# elements_v02.net
KiCad netlist of a schematic drawn in EAGLE
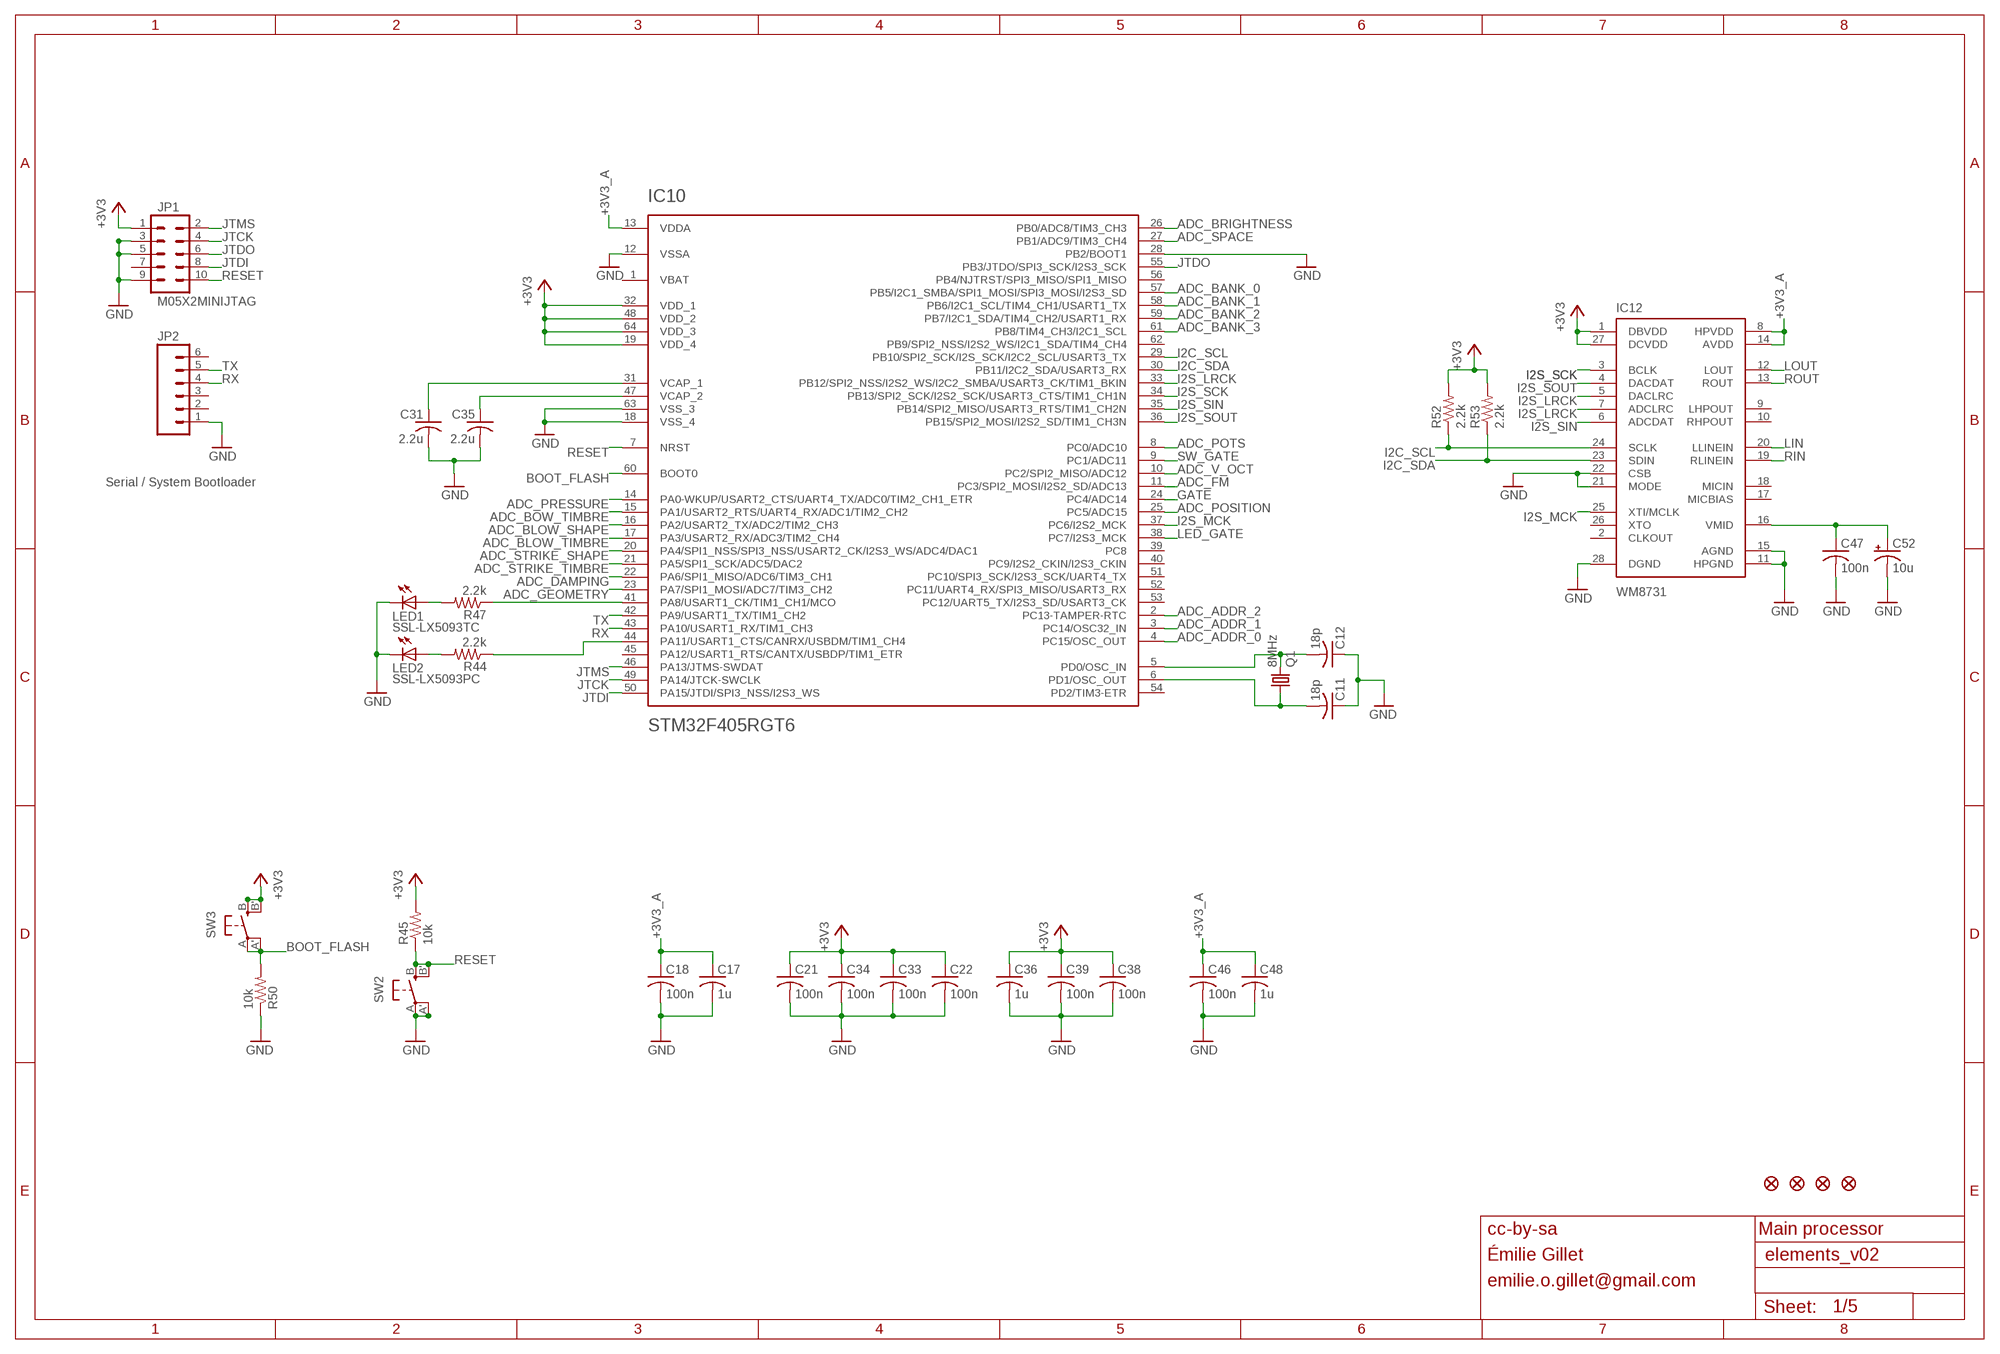
[diagram p0: schematic, sheet 1]
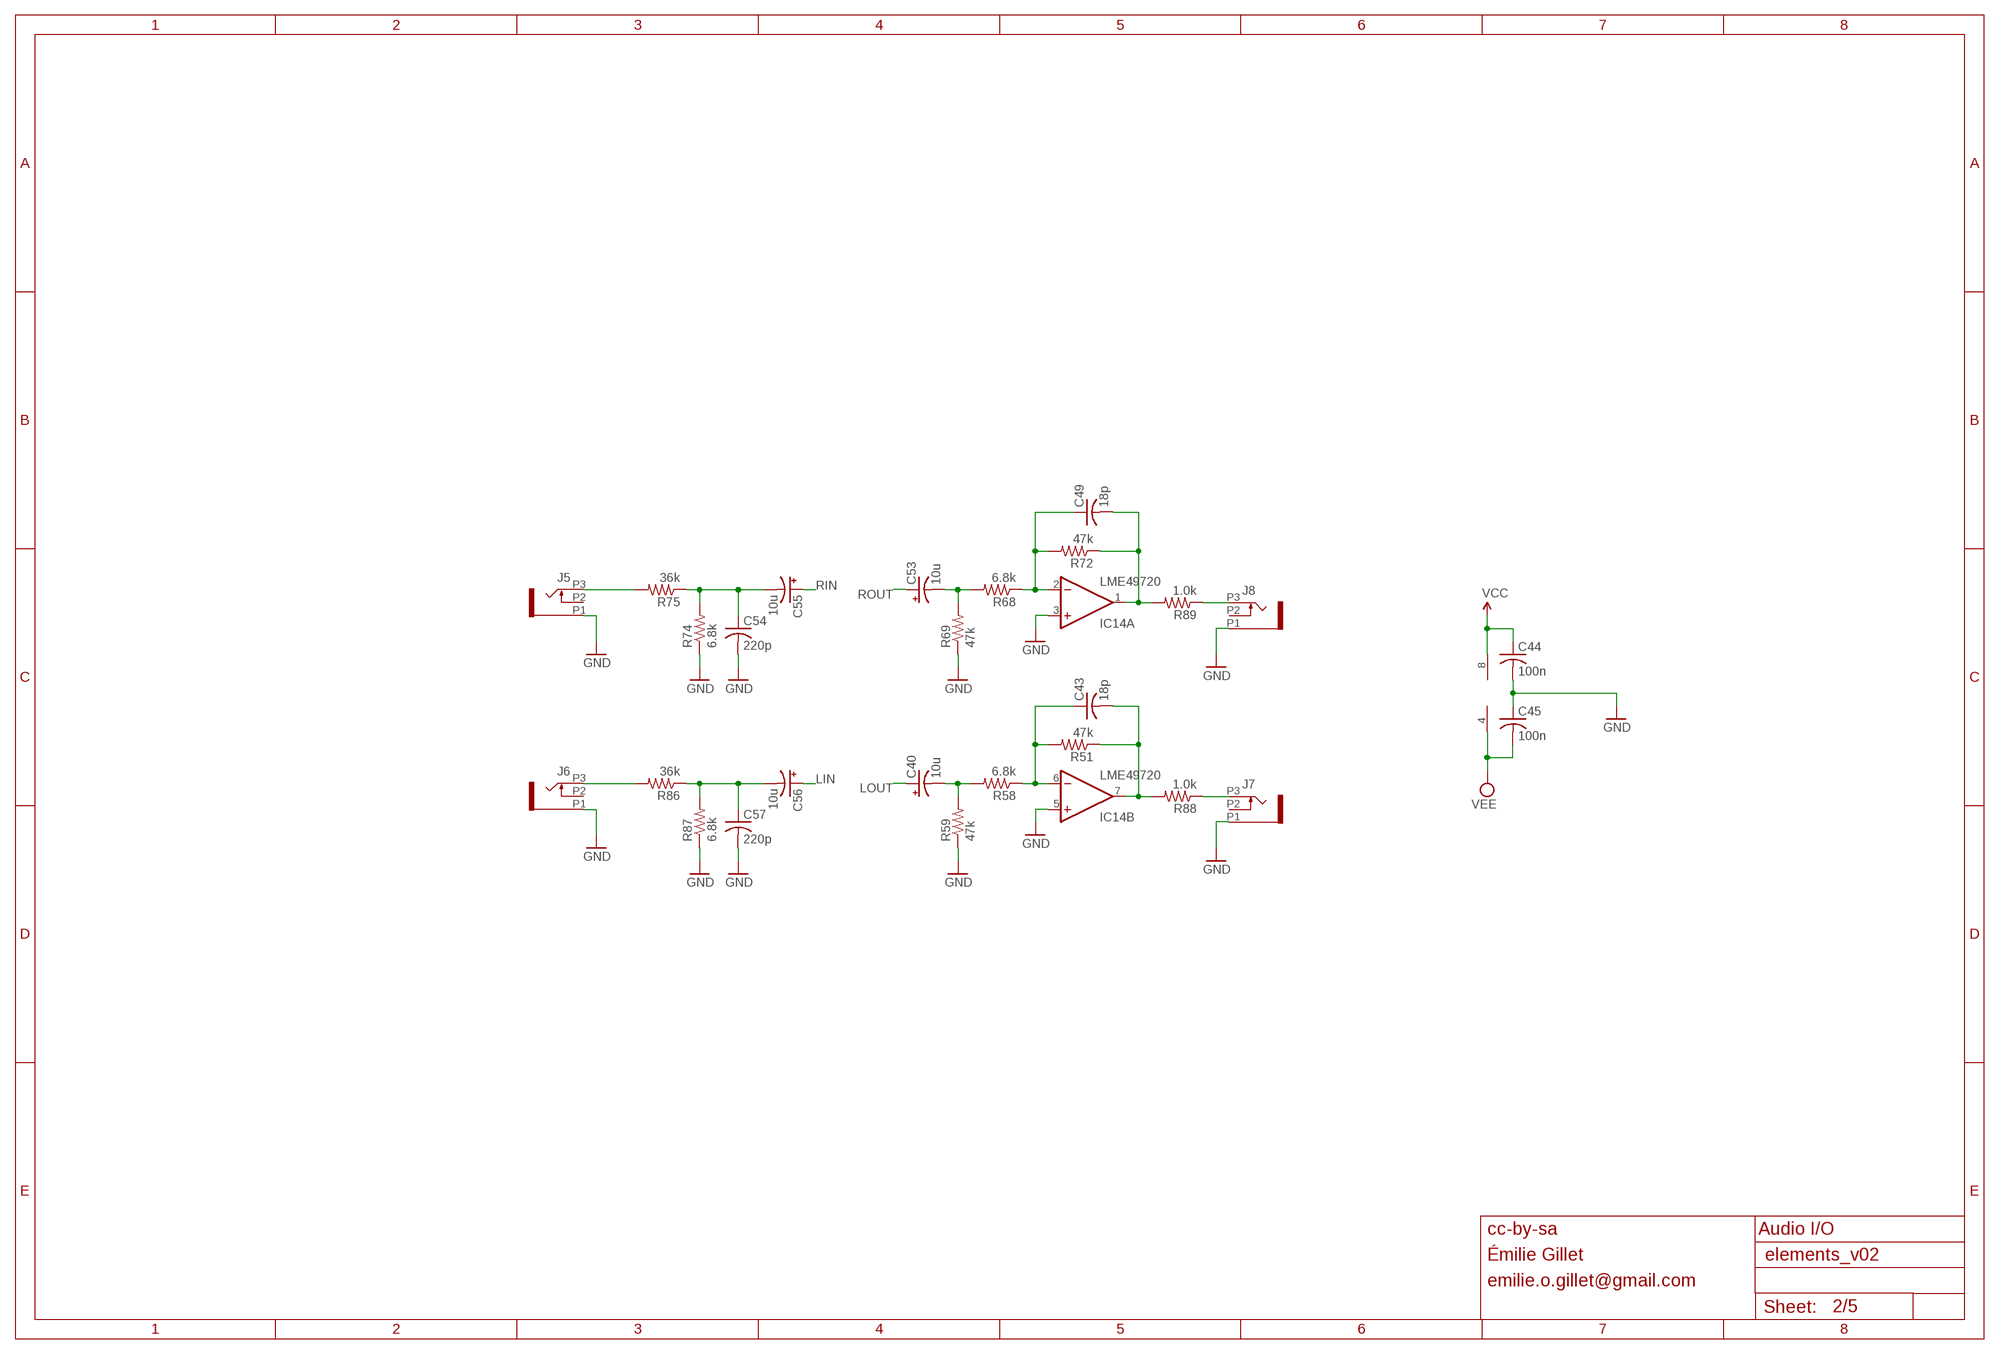
[diagram p1: schematic, sheet 2]
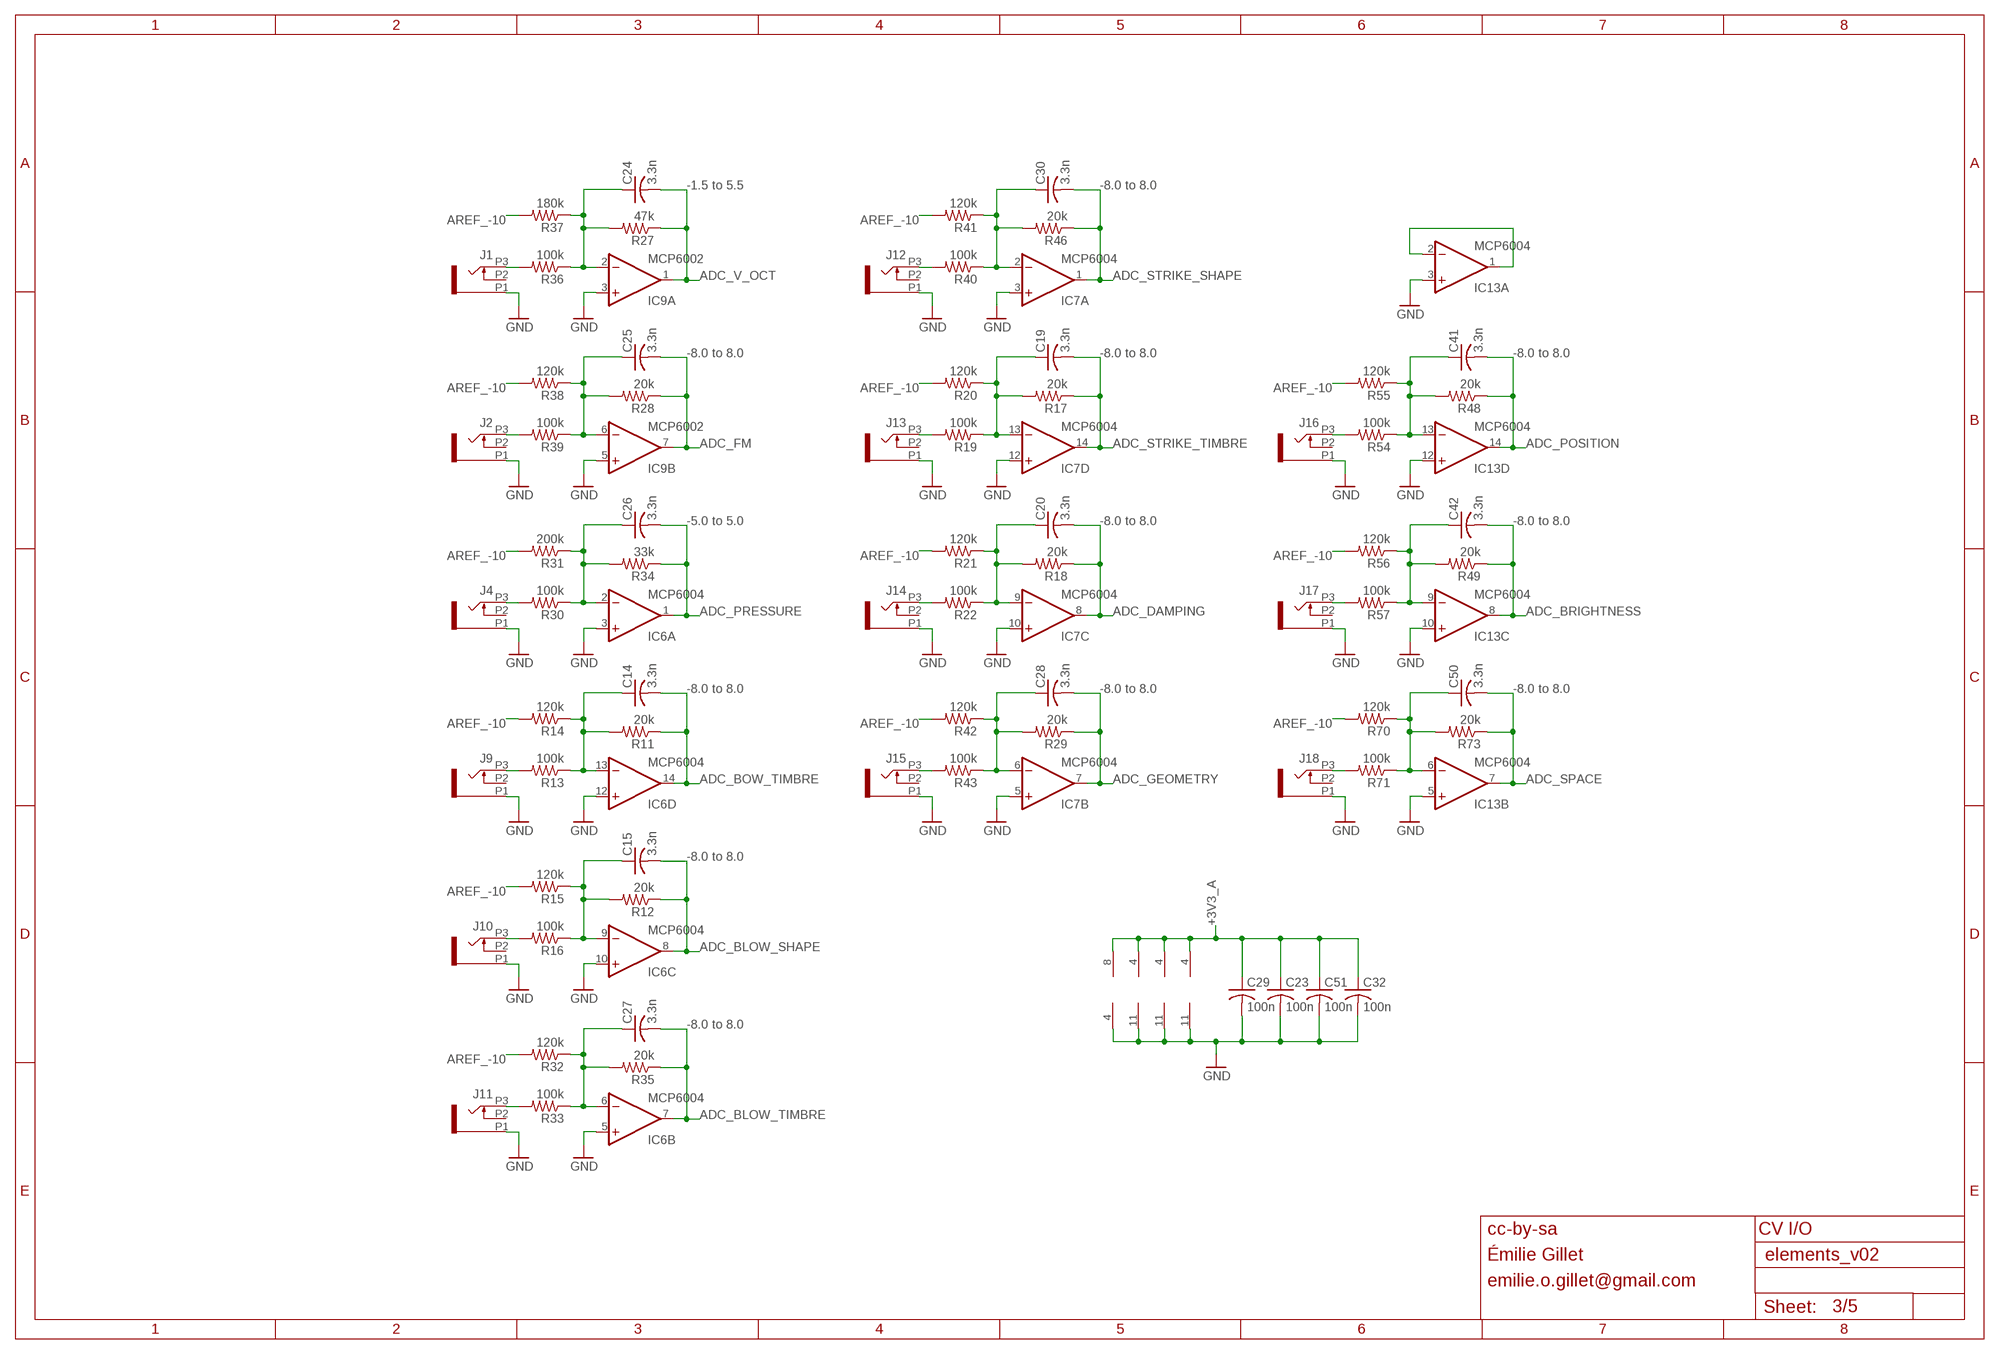
[diagram p2: schematic, sheet 3]
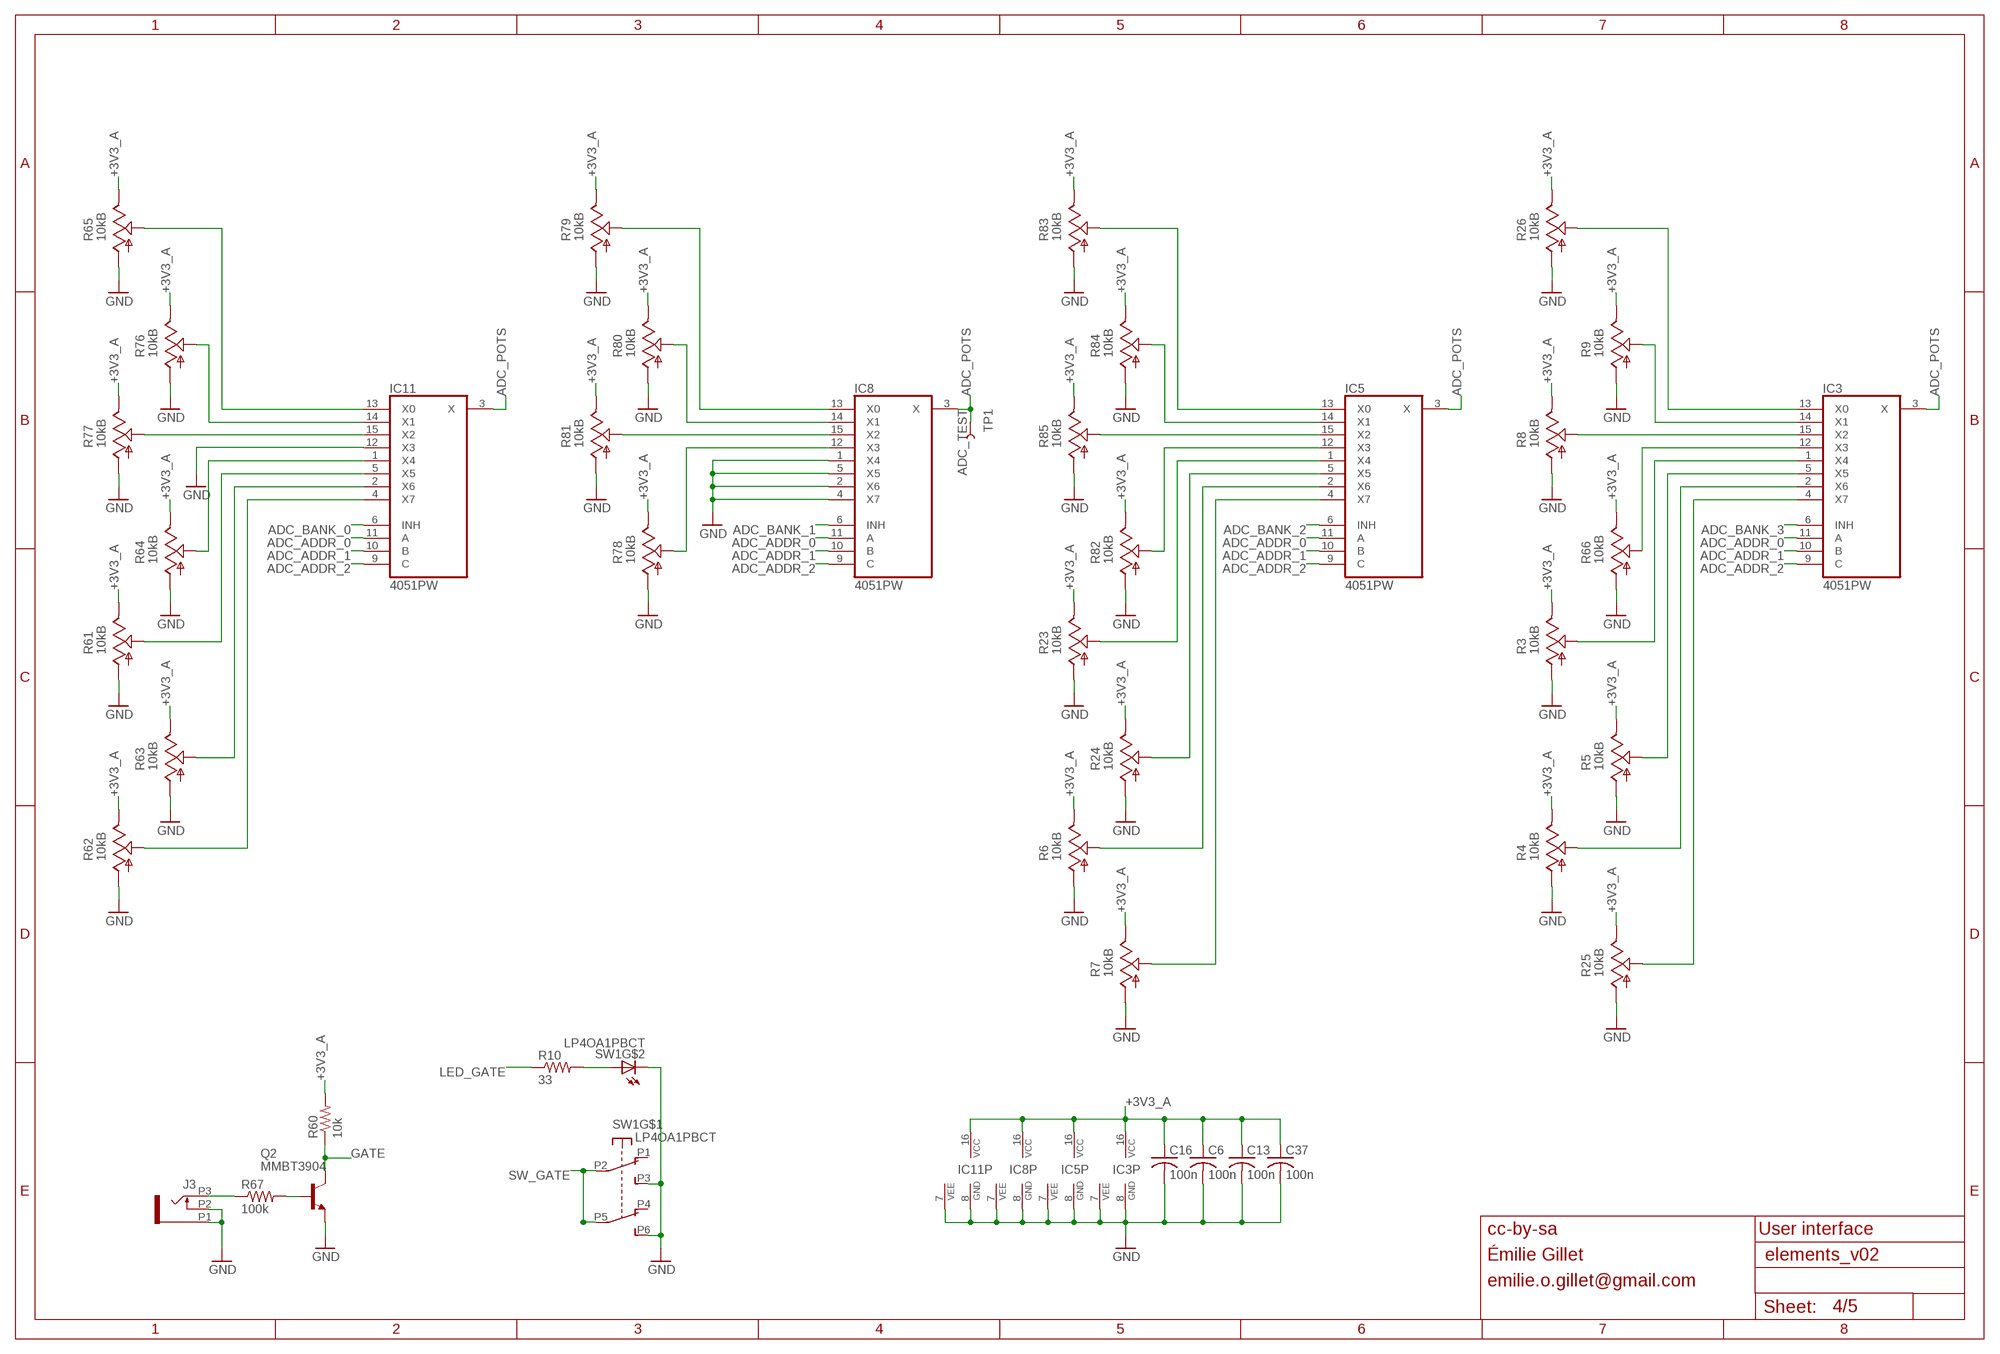
[diagram p3: schematic, sheet 4]
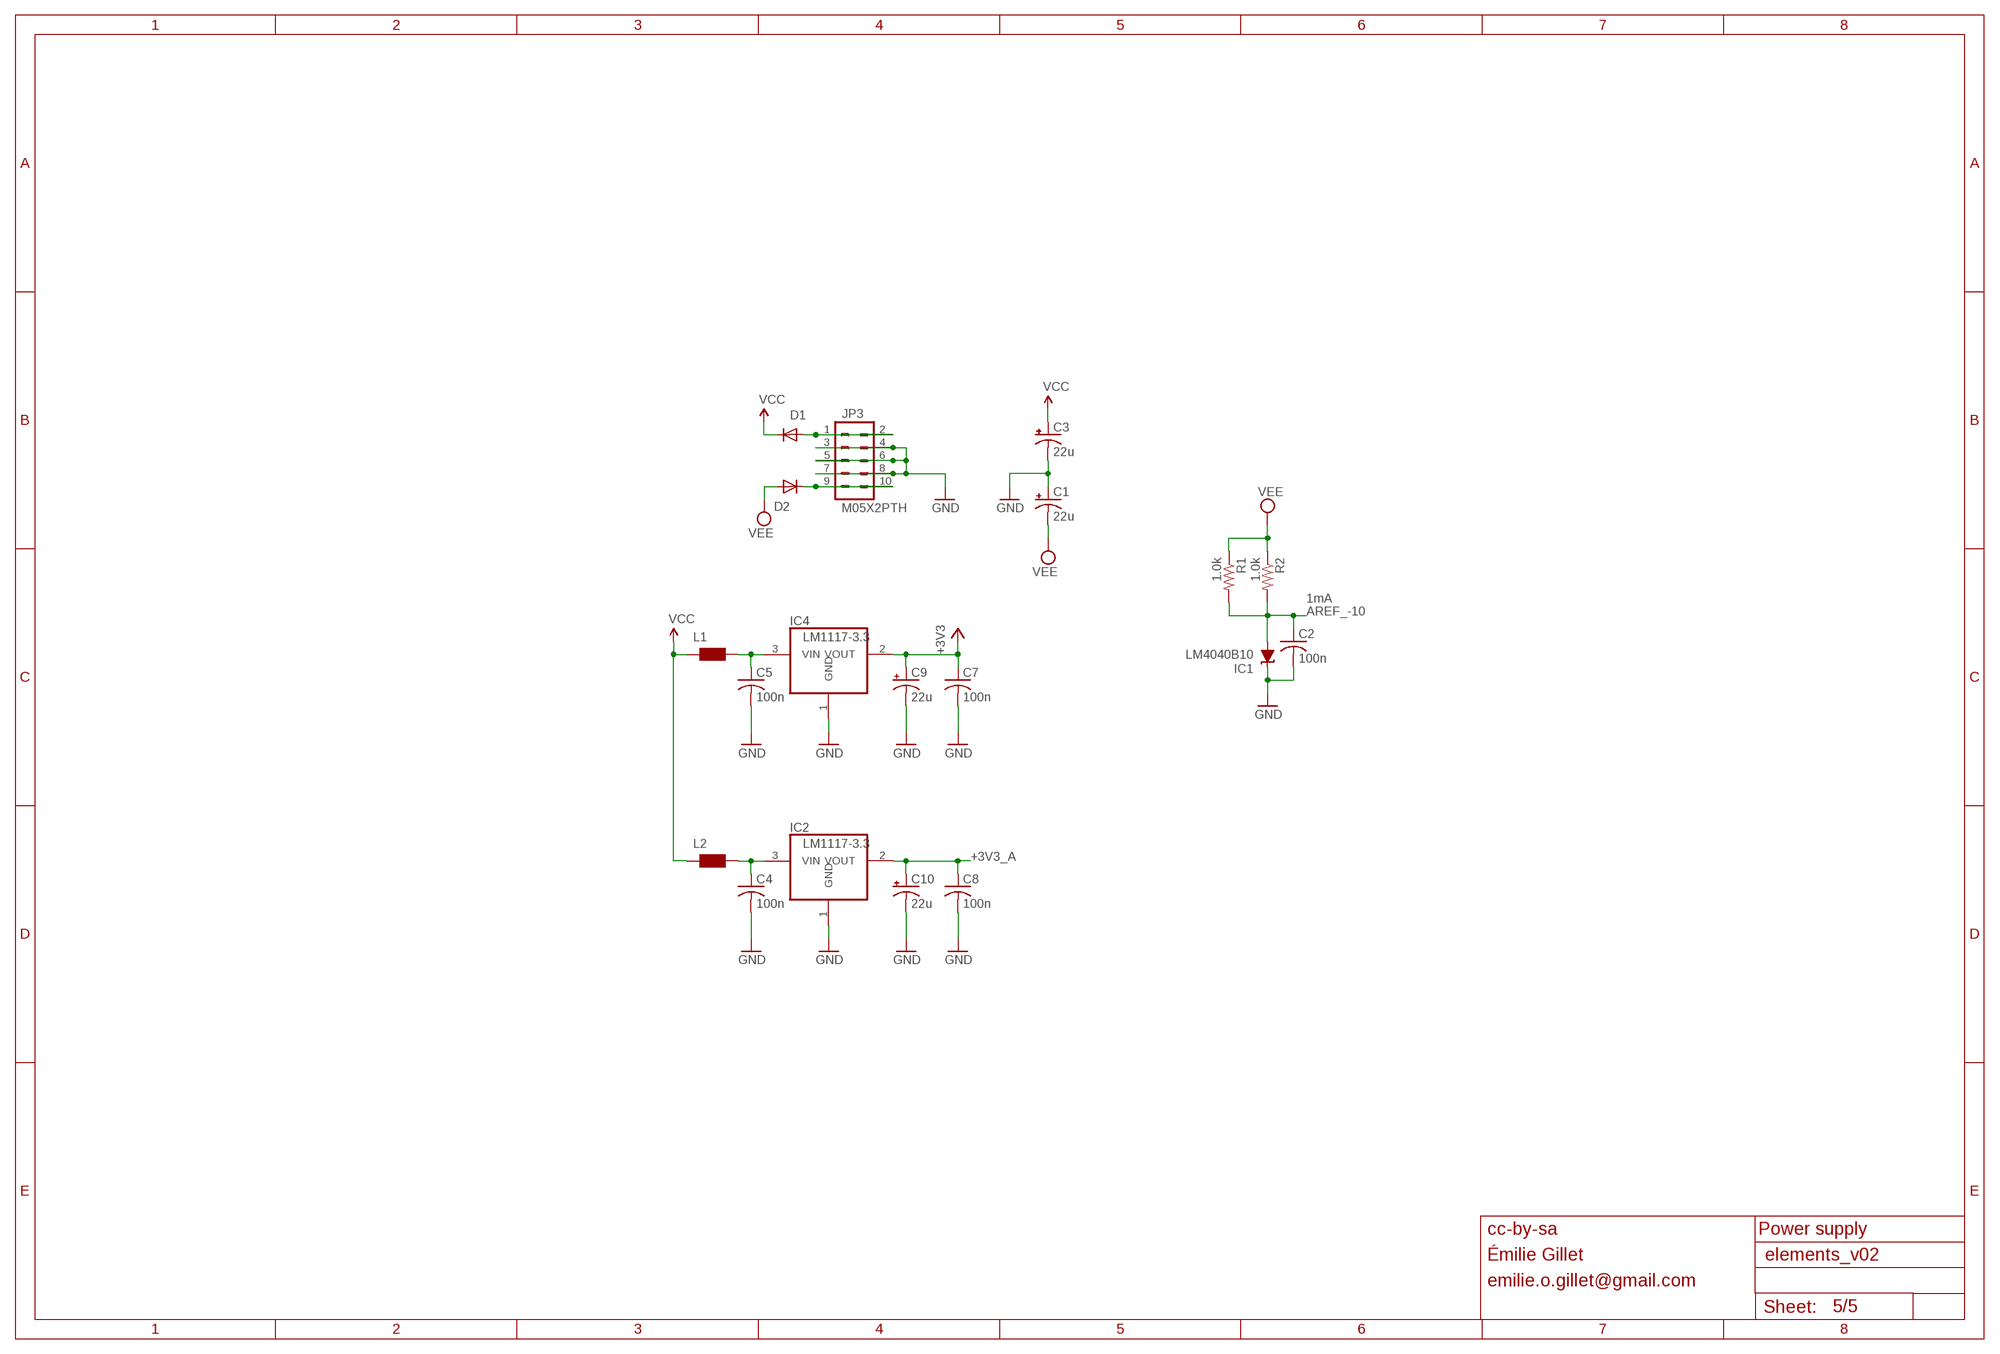
[diagram p4: schematic, sheet 5]

(export (version "E")
  (design (tool "Eeschema 10.0.6"))
  (components
    (comp (ref "C14")
      (value "3.3n")
      (footprint "eagle-import:C0603")
      (libsource (lib "eagle-import") (part "C-USC0603"))
    )
    (comp (ref "C15")
      (value "3.3n")
      (footprint "eagle-import:C0603")
      (libsource (lib "eagle-import") (part "C-USC0603"))
    )
    (comp (ref "C19")
      (value "3.3n")
      (footprint "eagle-import:C0603")
      (libsource (lib "eagle-import") (part "C-USC0603"))
    )
    (comp (ref "C20")
      (value "3.3n")
      (footprint "eagle-import:C0603")
      (libsource (lib "eagle-import") (part "C-USC0603"))
    )
    (comp (ref "C23")
      (value "100n")
      (footprint "eagle-import:C0603")
      (libsource (lib "eagle-import") (part "C-USC0603"))
    )
    (comp (ref "C24")
      (value "3.3n")
      (footprint "eagle-import:C0603")
      (libsource (lib "eagle-import") (part "C-USC0603"))
    )
    (comp (ref "C25")
      (value "3.3n")
      (footprint "eagle-import:C0603")
      (libsource (lib "eagle-import") (part "C-USC0603"))
    )
    (comp (ref "C26")
      (value "3.3n")
      (footprint "eagle-import:C0603")
      (libsource (lib "eagle-import") (part "C-USC0603"))
    )
    (comp (ref "C27")
      (value "3.3n")
      (footprint "eagle-import:C0603")
      (libsource (lib "eagle-import") (part "C-USC0603"))
    )
    (comp (ref "C28")
      (value "3.3n")
      (footprint "eagle-import:C0603")
      (libsource (lib "eagle-import") (part "C-USC0603"))
    )
    (comp (ref "C29")
      (value "100n")
      (footprint "eagle-import:C0603")
      (libsource (lib "eagle-import") (part "C-USC0603"))
    )
    (comp (ref "C30")
      (value "3.3n")
      (footprint "eagle-import:C0603")
      (libsource (lib "eagle-import") (part "C-USC0603"))
    )
    (comp (ref "C32")
      (value "100n")
      (footprint "eagle-import:C0603")
      (libsource (lib "eagle-import") (part "C-USC0603"))
    )
    (comp (ref "C41")
      (value "3.3n")
      (footprint "eagle-import:C0603")
      (libsource (lib "eagle-import") (part "C-USC0603"))
    )
    (comp (ref "C42")
      (value "3.3n")
      (footprint "eagle-import:C0603")
      (libsource (lib "eagle-import") (part "C-USC0603"))
    )
    (comp (ref "C50")
      (value "3.3n")
      (footprint "eagle-import:C0603")
      (libsource (lib "eagle-import") (part "C-USC0603"))
    )
    (comp (ref "C51")
      (value "100n")
      (footprint "eagle-import:C0603")
      (libsource (lib "eagle-import") (part "C-USC0603"))
    )
    (comp (ref "IC6")
      (value "MCP6004")
      (footprint "eagle-import:SO14")
      (libsource (lib "eagle-import") (part "TL074D"))
    )
    (comp (ref "IC7")
      (value "MCP6004")
      (footprint "eagle-import:SO14")
      (libsource (lib "eagle-import") (part "TL074D"))
    )
    (comp (ref "IC9")
      (value "MCP6002")
      (footprint "eagle-import:SO08")
      (libsource (lib "eagle-import") (part "TL072D"))
    )
    (comp (ref "IC13")
      (value "MCP6004")
      (footprint "eagle-import:SO14")
      (libsource (lib "eagle-import") (part "TL074D"))
    )
    (comp (ref "J1")
      (value "PJ301_THONKICONN6")
      (footprint "eagle-import:WQP_PJ_301M6")
      (libsource (lib "eagle-import") (part "PJ301_THONKICONN6"))
    )
    (comp (ref "J2")
      (value "PJ301_THONKICONN6")
      (footprint "eagle-import:WQP_PJ_301M6")
      (libsource (lib "eagle-import") (part "PJ301_THONKICONN6"))
    )
    (comp (ref "J4")
      (value "PJ301_THONKICONN6")
      (footprint "eagle-import:WQP_PJ_301M6")
      (libsource (lib "eagle-import") (part "PJ301_THONKICONN6"))
    )
    (comp (ref "J9")
      (value "PJ301_THONKICONN6")
      (footprint "eagle-import:WQP_PJ_301M6")
      (libsource (lib "eagle-import") (part "PJ301_THONKICONN6"))
    )
    (comp (ref "J10")
      (value "PJ301_THONKICONN6")
      (footprint "eagle-import:WQP_PJ_301M6")
      (libsource (lib "eagle-import") (part "PJ301_THONKICONN6"))
    )
    (comp (ref "J11")
      (value "PJ301_THONKICONN6")
      (footprint "eagle-import:WQP_PJ_301M6")
      (libsource (lib "eagle-import") (part "PJ301_THONKICONN6"))
    )
    (comp (ref "J12")
      (value "PJ301_THONKICONN6")
      (footprint "eagle-import:WQP_PJ_301M6")
      (libsource (lib "eagle-import") (part "PJ301_THONKICONN6"))
    )
    (comp (ref "J13")
      (value "PJ301_THONKICONN6")
      (footprint "eagle-import:WQP_PJ_301M6")
      (libsource (lib "eagle-import") (part "PJ301_THONKICONN6"))
    )
    (comp (ref "J14")
      (value "PJ301_THONKICONN6")
      (footprint "eagle-import:WQP_PJ_301M6")
      (libsource (lib "eagle-import") (part "PJ301_THONKICONN6"))
    )
    (comp (ref "J15")
      (value "PJ301_THONKICONN6")
      (footprint "eagle-import:WQP_PJ_301M6")
      (libsource (lib "eagle-import") (part "PJ301_THONKICONN6"))
    )
    (comp (ref "J16")
      (value "PJ301_THONKICONN6")
      (footprint "eagle-import:WQP_PJ_301M6")
      (libsource (lib "eagle-import") (part "PJ301_THONKICONN6"))
    )
    (comp (ref "J17")
      (value "PJ301_THONKICONN6")
      (footprint "eagle-import:WQP_PJ_301M6")
      (libsource (lib "eagle-import") (part "PJ301_THONKICONN6"))
    )
    (comp (ref "J18")
      (value "PJ301_THONKICONN6")
      (footprint "eagle-import:WQP_PJ_301M6")
      (libsource (lib "eagle-import") (part "PJ301_THONKICONN6"))
    )
    (comp (ref "R11")
      (value "20k")
      (footprint "eagle-import:R0603")
      (libsource (lib "eagle-import") (part "R-US_R0603"))
    )
    (comp (ref "R12")
      (value "20k")
      (footprint "eagle-import:R0603")
      (libsource (lib "eagle-import") (part "R-US_R0603"))
    )
    (comp (ref "R13")
      (value "100k")
      (footprint "eagle-import:R0603")
      (libsource (lib "eagle-import") (part "R-US_R0603"))
    )
    (comp (ref "R14")
      (value "120k")
      (footprint "eagle-import:R0603")
      (libsource (lib "eagle-import") (part "R-US_R0603"))
    )
    (comp (ref "R15")
      (value "120k")
      (footprint "eagle-import:R0603")
      (libsource (lib "eagle-import") (part "R-US_R0603"))
    )
    (comp (ref "R16")
      (value "100k")
      (footprint "eagle-import:R0603")
      (libsource (lib "eagle-import") (part "R-US_R0603"))
    )
    (comp (ref "R17")
      (value "20k")
      (footprint "eagle-import:R0603")
      (libsource (lib "eagle-import") (part "R-US_R0603"))
    )
    (comp (ref "R18")
      (value "20k")
      (footprint "eagle-import:R0603")
      (libsource (lib "eagle-import") (part "R-US_R0603"))
    )
    (comp (ref "R19")
      (value "100k")
      (footprint "eagle-import:R0603")
      (libsource (lib "eagle-import") (part "R-US_R0603"))
    )
    (comp (ref "R20")
      (value "120k")
      (footprint "eagle-import:R0603")
      (libsource (lib "eagle-import") (part "R-US_R0603"))
    )
    (comp (ref "R21")
      (value "120k")
      (footprint "eagle-import:R0603")
      (libsource (lib "eagle-import") (part "R-US_R0603"))
    )
    (comp (ref "R22")
      (value "100k")
      (footprint "eagle-import:R0603")
      (libsource (lib "eagle-import") (part "R-US_R0603"))
    )
    (comp (ref "R27")
      (value "47k")
      (footprint "eagle-import:R0603")
      (libsource (lib "eagle-import") (part "R-US_R0603"))
    )
    (comp (ref "R28")
      (value "20k")
      (footprint "eagle-import:R0603")
      (libsource (lib "eagle-import") (part "R-US_R0603"))
    )
    (comp (ref "R29")
      (value "20k")
      (footprint "eagle-import:R0603")
      (libsource (lib "eagle-import") (part "R-US_R0603"))
    )
    (comp (ref "R30")
      (value "100k")
      (footprint "eagle-import:R0603")
      (libsource (lib "eagle-import") (part "R-US_R0603"))
    )
    (comp (ref "R31")
      (value "200k")
      (footprint "eagle-import:R0603")
      (libsource (lib "eagle-import") (part "R-US_R0603"))
    )
    (comp (ref "R32")
      (value "120k")
      (footprint "eagle-import:R0603")
      (libsource (lib "eagle-import") (part "R-US_R0603"))
    )
    (comp (ref "R33")
      (value "100k")
      (footprint "eagle-import:R0603")
      (libsource (lib "eagle-import") (part "R-US_R0603"))
    )
    (comp (ref "R34")
      (value "33k")
      (footprint "eagle-import:R0603")
      (libsource (lib "eagle-import") (part "R-US_R0603"))
    )
    (comp (ref "R35")
      (value "20k")
      (footprint "eagle-import:R0603")
      (libsource (lib "eagle-import") (part "R-US_R0603"))
    )
    (comp (ref "R36")
      (value "100k")
      (footprint "eagle-import:R0603")
      (libsource (lib "eagle-import") (part "R-US_R0603"))
    )
    (comp (ref "R37")
      (value "180k")
      (footprint "eagle-import:R0603")
      (libsource (lib "eagle-import") (part "R-US_R0603"))
    )
    (comp (ref "R38")
      (value "120k")
      (footprint "eagle-import:R0603")
      (libsource (lib "eagle-import") (part "R-US_R0603"))
    )
    (comp (ref "R39")
      (value "100k")
      (footprint "eagle-import:R0603")
      (libsource (lib "eagle-import") (part "R-US_R0603"))
    )
    (comp (ref "R40")
      (value "100k")
      (footprint "eagle-import:R0603")
      (libsource (lib "eagle-import") (part "R-US_R0603"))
    )
    (comp (ref "R41")
      (value "120k")
      (footprint "eagle-import:R0603")
      (libsource (lib "eagle-import") (part "R-US_R0603"))
    )
    (comp (ref "R42")
      (value "120k")
      (footprint "eagle-import:R0603")
      (libsource (lib "eagle-import") (part "R-US_R0603"))
    )
    (comp (ref "R43")
      (value "100k")
      (footprint "eagle-import:R0603")
      (libsource (lib "eagle-import") (part "R-US_R0603"))
    )
    (comp (ref "R46")
      (value "20k")
      (footprint "eagle-import:R0603")
      (libsource (lib "eagle-import") (part "R-US_R0603"))
    )
    (comp (ref "R48")
      (value "20k")
      (footprint "eagle-import:R0603")
      (libsource (lib "eagle-import") (part "R-US_R0603"))
    )
    (comp (ref "R49")
      (value "20k")
      (footprint "eagle-import:R0603")
      (libsource (lib "eagle-import") (part "R-US_R0603"))
    )
    (comp (ref "R54")
      (value "100k")
      (footprint "eagle-import:R0603")
      (libsource (lib "eagle-import") (part "R-US_R0603"))
    )
    (comp (ref "R55")
      (value "120k")
      (footprint "eagle-import:R0603")
      (libsource (lib "eagle-import") (part "R-US_R0603"))
    )
    (comp (ref "R56")
      (value "120k")
      (footprint "eagle-import:R0603")
      (libsource (lib "eagle-import") (part "R-US_R0603"))
    )
    (comp (ref "R57")
      (value "100k")
      (footprint "eagle-import:R0603")
      (libsource (lib "eagle-import") (part "R-US_R0603"))
    )
    (comp (ref "R70")
      (value "120k")
      (footprint "eagle-import:R0603")
      (libsource (lib "eagle-import") (part "R-US_R0603"))
    )
    (comp (ref "R71")
      (value "100k")
      (footprint "eagle-import:R0603")
      (libsource (lib "eagle-import") (part "R-US_R0603"))
    )
    (comp (ref "R73")
      (value "20k")
      (footprint "eagle-import:R0603")
      (libsource (lib "eagle-import") (part "R-US_R0603"))
    )
    (comp (ref "C6")
      (value "100n")
      (footprint "eagle-import:C0603")
      (libsource (lib "eagle-import") (part "C-USC0603"))
    )
    (comp (ref "C13")
      (value "100n")
      (footprint "eagle-import:C0603")
      (libsource (lib "eagle-import") (part "C-USC0603"))
    )
    (comp (ref "C16")
      (value "100n")
      (footprint "eagle-import:C0603")
      (libsource (lib "eagle-import") (part "C-USC0603"))
    )
    (comp (ref "C37")
      (value "100n")
      (footprint "eagle-import:C0603")
      (libsource (lib "eagle-import") (part "C-USC0603"))
    )
    (comp (ref "IC3")
      (value "4051PW")
      (footprint "eagle-import:TSSOP16")
      (libsource (lib "eagle-import") (part "4051PW"))
    )
    (comp (ref "IC5")
      (value "4051PW")
      (footprint "eagle-import:TSSOP16")
      (libsource (lib "eagle-import") (part "4051PW"))
    )
    (comp (ref "IC8")
      (value "4051PW")
      (footprint "eagle-import:TSSOP16")
      (libsource (lib "eagle-import") (part "4051PW"))
    )
    (comp (ref "IC11")
      (value "4051PW")
      (footprint "eagle-import:TSSOP16")
      (libsource (lib "eagle-import") (part "4051PW"))
    )
    (comp (ref "J3")
      (value "PJ301_THONKICONN6")
      (footprint "eagle-import:WQP_PJ_301M6")
      (libsource (lib "eagle-import") (part "PJ301_THONKICONN6"))
    )
    (comp (ref "Q2")
      (value "MMBT3904")
      (footprint "eagle-import:SOT23-BEC")
      (libsource (lib "eagle-import") (part "-NPN-SOT23-BECMMBT3904LT1"))
    )
    (comp (ref "R3")
      (value "10kB")
      (footprint "eagle-import:ALPS_POT_VERTICAL_PS")
      (libsource (lib "eagle-import") (part "POT_USVERTICAL_PS"))
    )
    (comp (ref "R4")
      (value "10kB")
      (footprint "eagle-import:ALPS_POT_VERTICAL_PS")
      (libsource (lib "eagle-import") (part "POT_USVERTICAL_PS"))
    )
    (comp (ref "R5")
      (value "10kB")
      (footprint "eagle-import:ALPS_POT_VERTICAL_PS")
      (libsource (lib "eagle-import") (part "POT_USVERTICAL_PS"))
    )
    (comp (ref "R6")
      (value "10kB")
      (footprint "eagle-import:ALPS_POT_VERTICAL_PS")
      (libsource (lib "eagle-import") (part "POT_USVERTICAL_PS"))
    )
    (comp (ref "R7")
      (value "10kB")
      (footprint "eagle-import:ALPS_POT_VERTICAL_PS")
      (libsource (lib "eagle-import") (part "POT_USVERTICAL_PS"))
    )
    (comp (ref "R8")
      (value "10kB")
      (footprint "eagle-import:ALPS_POT_VERTICAL_PS")
      (libsource (lib "eagle-import") (part "POT_USVERTICAL_PS"))
    )
    (comp (ref "R9")
      (value "10kB")
      (footprint "eagle-import:ALPS_POT_VERTICAL_PS")
      (libsource (lib "eagle-import") (part "POT_USVERTICAL_PS"))
    )
    (comp (ref "R10")
      (value "33")
      (footprint "eagle-import:R0603")
      (libsource (lib "eagle-import") (part "R-US_R0603"))
    )
    (comp (ref "R23")
      (value "10kB")
      (footprint "eagle-import:ALPS_POT_VERTICAL_PS")
      (libsource (lib "eagle-import") (part "POT_USVERTICAL_PS"))
    )
    (comp (ref "R24")
      (value "10kB")
      (footprint "eagle-import:ALPS_POT_VERTICAL_PS")
      (libsource (lib "eagle-import") (part "POT_USVERTICAL_PS"))
    )
    (comp (ref "R25")
      (value "10kB")
      (footprint "eagle-import:ALPS_POT_VERTICAL_PS")
      (libsource (lib "eagle-import") (part "POT_USVERTICAL_PS"))
    )
    (comp (ref "R26")
      (value "10kB")
      (footprint "eagle-import:ALPS_POT_VERTICAL_PS")
      (libsource (lib "eagle-import") (part "POT_USVERTICAL_PS"))
    )
    (comp (ref "R60")
      (value "10k")
      (footprint "eagle-import:R0603")
      (libsource (lib "eagle-import") (part "R-US_R0603"))
    )
    (comp (ref "R61")
      (value "10kB")
      (footprint "eagle-import:ALPS_POT_VERTICAL_PS")
      (libsource (lib "eagle-import") (part "POT_USVERTICAL_PS"))
    )
    (comp (ref "R62")
      (value "10kB")
      (footprint "eagle-import:ALPS_POT_VERTICAL_PS")
      (libsource (lib "eagle-import") (part "POT_USVERTICAL_PS"))
    )
    (comp (ref "R63")
      (value "10kB")
      (footprint "eagle-import:ALPS_POT_VERTICAL_PS")
      (libsource (lib "eagle-import") (part "POT_USVERTICAL_PS"))
    )
    (comp (ref "R64")
      (value "10kB")
      (footprint "eagle-import:ALPS_POT_VERTICAL_PS")
      (libsource (lib "eagle-import") (part "POT_USVERTICAL_PS"))
    )
    (comp (ref "R65")
      (value "10kB")
      (footprint "eagle-import:ALPS_POT_VERTICAL_PS")
      (libsource (lib "eagle-import") (part "POT_USVERTICAL_PS"))
    )
    (comp (ref "R66")
      (value "10kB")
      (footprint "eagle-import:ALPS_POT_VERTICAL_PS")
      (libsource (lib "eagle-import") (part "POT_USVERTICAL_PS"))
    )
    (comp (ref "R67")
      (value "100k")
      (footprint "eagle-import:R0603")
      (libsource (lib "eagle-import") (part "R-US_R0603"))
    )
    (comp (ref "R76")
      (value "10kB")
      (footprint "eagle-import:ALPS_POT_VERTICAL")
      (libsource (lib "eagle-import") (part "POT_USVERTICAL"))
    )
    (comp (ref "R77")
      (value "10kB")
      (footprint "eagle-import:ALPS_POT_VERTICAL")
      (libsource (lib "eagle-import") (part "POT_USVERTICAL"))
    )
    (comp (ref "R78")
      (value "10kB")
      (footprint "eagle-import:ALPS_POT_VERTICAL")
      (libsource (lib "eagle-import") (part "POT_USVERTICAL"))
    )
    (comp (ref "R79")
      (value "10kB")
      (footprint "eagle-import:ALPS_POT_VERTICAL")
      (libsource (lib "eagle-import") (part "POT_USVERTICAL"))
    )
    (comp (ref "R80")
      (value "10kB")
      (footprint "eagle-import:ALPS_POT_VERTICAL")
      (libsource (lib "eagle-import") (part "POT_USVERTICAL"))
    )
    (comp (ref "R81")
      (value "10kB")
      (footprint "eagle-import:ALPS_POT_VERTICAL")
      (libsource (lib "eagle-import") (part "POT_USVERTICAL"))
    )
    (comp (ref "R82")
      (value "10kB")
      (footprint "eagle-import:ALPS_POT_VERTICAL")
      (libsource (lib "eagle-import") (part "POT_USVERTICAL"))
    )
    (comp (ref "R83")
      (value "10kB")
      (footprint "eagle-import:ALPS_POT_VERTICAL")
      (libsource (lib "eagle-import") (part "POT_USVERTICAL"))
    )
    (comp (ref "R84")
      (value "10kB")
      (footprint "eagle-import:ALPS_POT_VERTICAL")
      (libsource (lib "eagle-import") (part "POT_USVERTICAL"))
    )
    (comp (ref "R85")
      (value "10kB")
      (footprint "eagle-import:ALPS_POT_VERTICAL")
      (libsource (lib "eagle-import") (part "POT_USVERTICAL"))
    )
    (comp (ref "SW1")
      (value "LP4OA1PBCT")
      (footprint "eagle-import:LP4OA1PBCT")
      (libsource (lib "eagle-import") (part "LP4OA1PBCT"))
    )
    (comp (ref "TP1")
      (value "ADC_TEST")
      (footprint "eagle-import:PAD.03X.03")
      (libsource (lib "eagle-import") (part "TEST-POINT3"))
    )
    (comp (ref "C1")
      (value "22u")
      (footprint "eagle-import:PANASONIC_C")
      (libsource (lib "eagle-import") (part "CPOL-USC"))
    )
    (comp (ref "C2")
      (value "100n")
      (footprint "eagle-import:C0603")
      (libsource (lib "eagle-import") (part "C-USC0603"))
    )
    (comp (ref "C3")
      (value "22u")
      (footprint "eagle-import:PANASONIC_C")
      (libsource (lib "eagle-import") (part "CPOL-USC"))
    )
    (comp (ref "C4")
      (value "100n")
      (footprint "eagle-import:C0603")
      (libsource (lib "eagle-import") (part "C-USC0603"))
    )
    (comp (ref "C5")
      (value "100n")
      (footprint "eagle-import:C0603")
      (libsource (lib "eagle-import") (part "C-USC0603"))
    )
    (comp (ref "C7")
      (value "100n")
      (footprint "eagle-import:C0603")
      (libsource (lib "eagle-import") (part "C-USC0603"))
    )
    (comp (ref "C8")
      (value "100n")
      (footprint "eagle-import:C0603")
      (libsource (lib "eagle-import") (part "C-USC0603"))
    )
    (comp (ref "C9")
      (value "22u")
      (footprint "eagle-import:PANASONIC_C")
      (libsource (lib "eagle-import") (part "CPOL-USC"))
    )
    (comp (ref "C10")
      (value "22u")
      (footprint "eagle-import:PANASONIC_C")
      (libsource (lib "eagle-import") (part "CPOL-USC"))
    )
    (comp (ref "D1")
      (value "1N5819HW")
      (footprint "eagle-import:SOD123")
      (libsource (lib "eagle-import") (part "DIODE-SOD123"))
    )
    (comp (ref "D2")
      (value "1N5819HW")
      (footprint "eagle-import:SOD123")
      (libsource (lib "eagle-import") (part "DIODE-SOD123"))
    )
    (comp (ref "IC1")
      (value "LM4040B10")
      (footprint "eagle-import:DBZ_R-PDSO-G3")
      (libsource (lib "eagle-import") (part "LM4041DBZB12"))
    )
    (comp (ref "IC2")
      (value "LM1117-3.3")
      (footprint "eagle-import:SOT223")
      (libsource (lib "eagle-import") (part "REG1117"))
    )
    (comp (ref "IC4")
      (value "LM1117-3.3")
      (footprint "eagle-import:SOT223")
      (libsource (lib "eagle-import") (part "REG1117"))
    )
    (comp (ref "JP3")
      (value "M05X2PTH")
      (footprint "eagle-import:AVR_ICSP")
      (libsource (lib "eagle-import") (part "M05X2PTH"))
    )
    (comp (ref "L1")
      (value "WE-CBF_0603")
      (footprint "eagle-import:0603")
      (libsource (lib "eagle-import") (part "WE-CBF_0603"))
    )
    (comp (ref "L2")
      (value "WE-CBF_0603")
      (footprint "eagle-import:0603")
      (libsource (lib "eagle-import") (part "WE-CBF_0603"))
    )
    (comp (ref "R1")
      (value "1.0k")
      (footprint "eagle-import:R0603")
      (libsource (lib "eagle-import") (part "R-US_R0603"))
    )
    (comp (ref "R2")
      (value "1.0k")
      (footprint "eagle-import:R0603")
      (libsource (lib "eagle-import") (part "R-US_R0603"))
    )
    (comp (ref "C11")
      (value "18p")
      (footprint "eagle-import:C0603")
      (libsource (lib "eagle-import") (part "C-USC0603"))
    )
    (comp (ref "C12")
      (value "18p")
      (footprint "eagle-import:C0603")
      (libsource (lib "eagle-import") (part "C-USC0603"))
    )
    (comp (ref "C17")
      (value "1u")
      (footprint "eagle-import:C0603")
      (libsource (lib "eagle-import") (part "C-USC0603"))
    )
    (comp (ref "C18")
      (value "100n")
      (footprint "eagle-import:C0603")
      (libsource (lib "eagle-import") (part "C-USC0603"))
    )
    (comp (ref "C21")
      (value "100n")
      (footprint "eagle-import:C0603")
      (libsource (lib "eagle-import") (part "C-USC0603"))
    )
    (comp (ref "C22")
      (value "100n")
      (footprint "eagle-import:C0603")
      (libsource (lib "eagle-import") (part "C-USC0603"))
    )
    (comp (ref "C31")
      (value "2.2u")
      (footprint "eagle-import:C0805")
      (libsource (lib "eagle-import") (part "C-USC0805"))
    )
    (comp (ref "C33")
      (value "100n")
      (footprint "eagle-import:C0603")
      (libsource (lib "eagle-import") (part "C-USC0603"))
    )
    (comp (ref "C34")
      (value "100n")
      (footprint "eagle-import:C0603")
      (libsource (lib "eagle-import") (part "C-USC0603"))
    )
    (comp (ref "C35")
      (value "2.2u")
      (footprint "eagle-import:C0805")
      (libsource (lib "eagle-import") (part "C-USC0805"))
    )
    (comp (ref "C36")
      (value "1u")
      (footprint "eagle-import:C0603")
      (libsource (lib "eagle-import") (part "C-USC0603"))
    )
    (comp (ref "C38")
      (value "100n")
      (footprint "eagle-import:C0603")
      (libsource (lib "eagle-import") (part "C-USC0603"))
    )
    (comp (ref "C39")
      (value "100n")
      (footprint "eagle-import:C0603")
      (libsource (lib "eagle-import") (part "C-USC0603"))
    )
    (comp (ref "C46")
      (value "100n")
      (footprint "eagle-import:C0603")
      (libsource (lib "eagle-import") (part "C-USC0603"))
    )
    (comp (ref "C47")
      (value "100n")
      (footprint "eagle-import:C0603")
      (libsource (lib "eagle-import") (part "C-USC0603"))
    )
    (comp (ref "C48")
      (value "1u")
      (footprint "eagle-import:C0603")
      (libsource (lib "eagle-import") (part "C-USC0603"))
    )
    (comp (ref "C52")
      (value "10u")
      (footprint "eagle-import:PANASONIC_B")
      (libsource (lib "eagle-import") (part "CPOL-USB"))
    )
    (comp (ref "F1")
      (value "FIDUCIAL1X2")
      (footprint "eagle-import:FIDUCIAL-1X2")
      (libsource (lib "eagle-import") (part "FIDUCIAL1X2"))
    )
    (comp (ref "F2")
      (value "FIDUCIAL1X2")
      (footprint "eagle-import:FIDUCIAL-1X2")
      (libsource (lib "eagle-import") (part "FIDUCIAL1X2"))
    )
    (comp (ref "F3")
      (value "FIDUCIAL1X2")
      (footprint "eagle-import:FIDUCIAL-1X2")
      (libsource (lib "eagle-import") (part "FIDUCIAL1X2"))
    )
    (comp (ref "F4")
      (value "FIDUCIAL1X2")
      (footprint "eagle-import:FIDUCIAL-1X2")
      (libsource (lib "eagle-import") (part "FIDUCIAL1X2"))
    )
    (comp (ref "IC10")
      (value "STM32F405RGT6")
      (footprint "eagle-import:TQFP-10X10-64")
      (libsource (lib "eagle-import") (part "STM32F20X"))
    )
    (comp (ref "IC12")
      (value "WM8731")
      (footprint "eagle-import:SSOP28")
      (libsource (lib "eagle-import") (part "WM8731"))
    )
    (comp (ref "JP1")
      (value "M05X2MINIJTAG")
      (footprint "eagle-import:2X5-1.27")
      (libsource (lib "eagle-import") (part "M05X2MINIJTAG"))
    )
    (comp (ref "JP2")
      (value "M06SIP")
      (footprint "eagle-import:1X06")
      (libsource (lib "eagle-import") (part "M06SIP"))
    )
    (comp (ref "LED1")
      (value "SSL-LX5093TC")
      (footprint "eagle-import:LED5MM")
      (libsource (lib "eagle-import") (part "LED5MM"))
    )
    (comp (ref "LED2")
      (value "SSL-LX5093PC")
      (footprint "eagle-import:LED5MM")
      (libsource (lib "eagle-import") (part "LED5MM"))
    )
    (comp (ref "Q1")
      (value "8MHz")
      (footprint "eagle-import:HC49UP")
      (libsource (lib "eagle-import") (part "CRYSTALHC49UP"))
    )
    (comp (ref "R44")
      (value "2.2k")
      (footprint "eagle-import:R0603")
      (libsource (lib "eagle-import") (part "R-US_R0603"))
    )
    (comp (ref "R45")
      (value "10k")
      (footprint "eagle-import:R0603")
      (libsource (lib "eagle-import") (part "R-US_R0603"))
    )
    (comp (ref "R47")
      (value "2.2k")
      (footprint "eagle-import:R0603")
      (libsource (lib "eagle-import") (part "R-US_R0603"))
    )
    (comp (ref "R50")
      (value "10k")
      (footprint "eagle-import:R0603")
      (libsource (lib "eagle-import") (part "R-US_R0603"))
    )
    (comp (ref "R52")
      (value "2.2k")
      (footprint "eagle-import:R0603")
      (libsource (lib "eagle-import") (part "R-US_R0603"))
    )
    (comp (ref "R53")
      (value "2.2k")
      (footprint "eagle-import:R0603")
      (libsource (lib "eagle-import") (part "R-US_R0603"))
    )
    (comp (ref "SW2")
      (value "EVQQ2")
      (footprint "eagle-import:EVQ-Q2")
      (libsource (lib "eagle-import") (part "EVQQ2"))
    )
    (comp (ref "SW3")
      (value "EVQQ2")
      (footprint "eagle-import:EVQ-Q2")
      (libsource (lib "eagle-import") (part "EVQQ2"))
    )
    (comp (ref "C40")
      (value "10u")
      (footprint "eagle-import:PANASONIC_B")
      (libsource (lib "eagle-import") (part "CPOL-USB"))
    )
    (comp (ref "C43")
      (value "18p")
      (footprint "eagle-import:C0603")
      (libsource (lib "eagle-import") (part "C-USC0603"))
    )
    (comp (ref "C44")
      (value "100n")
      (footprint "eagle-import:C0603")
      (libsource (lib "eagle-import") (part "C-USC0603"))
    )
    (comp (ref "C45")
      (value "100n")
      (footprint "eagle-import:C0603")
      (libsource (lib "eagle-import") (part "C-USC0603"))
    )
    (comp (ref "C49")
      (value "18p")
      (footprint "eagle-import:C0603")
      (libsource (lib "eagle-import") (part "C-USC0603"))
    )
    (comp (ref "C53")
      (value "10u")
      (footprint "eagle-import:PANASONIC_B")
      (libsource (lib "eagle-import") (part "CPOL-USB"))
    )
    (comp (ref "C54")
      (value "220p")
      (footprint "eagle-import:C0603")
      (libsource (lib "eagle-import") (part "C-USC0603"))
    )
    (comp (ref "C55")
      (value "10u")
      (footprint "eagle-import:PANASONIC_B")
      (libsource (lib "eagle-import") (part "CPOL-USB"))
    )
    (comp (ref "C56")
      (value "10u")
      (footprint "eagle-import:PANASONIC_B")
      (libsource (lib "eagle-import") (part "CPOL-USB"))
    )
    (comp (ref "C57")
      (value "220p")
      (footprint "eagle-import:C0603")
      (libsource (lib "eagle-import") (part "C-USC0603"))
    )
    (comp (ref "IC14")
      (value "LME49720")
      (footprint "eagle-import:SO08")
      (libsource (lib "eagle-import") (part "og-linear_TL072D"))
    )
    (comp (ref "J5")
      (value "PJ301_THONKICONN6")
      (footprint "eagle-import:WQP_PJ_301M6")
      (libsource (lib "eagle-import") (part "PJ301_THONKICONN6"))
    )
    (comp (ref "J6")
      (value "PJ301_THONKICONN6")
      (footprint "eagle-import:WQP_PJ_301M6")
      (libsource (lib "eagle-import") (part "PJ301_THONKICONN6"))
    )
    (comp (ref "J7")
      (value "PJ301_THONKICONN6")
      (footprint "eagle-import:WQP_PJ_301M6")
      (libsource (lib "eagle-import") (part "PJ301_THONKICONN6"))
    )
    (comp (ref "J8")
      (value "PJ301_THONKICONN6")
      (footprint "eagle-import:WQP_PJ_301M6")
      (libsource (lib "eagle-import") (part "PJ301_THONKICONN6"))
    )
    (comp (ref "R51")
      (value "47k")
      (footprint "eagle-import:R0603")
      (libsource (lib "eagle-import") (part "R-US_R0603"))
    )
    (comp (ref "R58")
      (value "6.8k")
      (footprint "eagle-import:R0603")
      (libsource (lib "eagle-import") (part "R-US_R0603"))
    )
    (comp (ref "R59")
      (value "47k")
      (footprint "eagle-import:R0603")
      (libsource (lib "eagle-import") (part "R-US_R0603"))
    )
    (comp (ref "R68")
      (value "6.8k")
      (footprint "eagle-import:R0603")
      (libsource (lib "eagle-import") (part "R-US_R0603"))
    )
    (comp (ref "R69")
      (value "47k")
      (footprint "eagle-import:R0603")
      (libsource (lib "eagle-import") (part "R-US_R0603"))
    )
    (comp (ref "R72")
      (value "47k")
      (footprint "eagle-import:R0603")
      (libsource (lib "eagle-import") (part "R-US_R0603"))
    )
    (comp (ref "R74")
      (value "6.8k")
      (footprint "eagle-import:R0603")
      (libsource (lib "eagle-import") (part "R-US_R0603"))
    )
    (comp (ref "R75")
      (value "36k")
      (footprint "eagle-import:R0603")
      (libsource (lib "eagle-import") (part "R-US_R0603"))
    )
    (comp (ref "R86")
      (value "36k")
      (footprint "eagle-import:R0603")
      (libsource (lib "eagle-import") (part "R-US_R0603"))
    )
    (comp (ref "R87")
      (value "6.8k")
      (footprint "eagle-import:R0603")
      (libsource (lib "eagle-import") (part "R-US_R0603"))
    )
    (comp (ref "R88")
      (value "1.0k")
      (footprint "eagle-import:R0603")
      (libsource (lib "eagle-import") (part "R-US_R0603"))
    )
    (comp (ref "R89")
      (value "1.0k")
      (footprint "eagle-import:R0603")
      (libsource (lib "eagle-import") (part "R-US_R0603"))
    )
  )
  (nets
    (net (code "1") (name "+3V3") (class "Default")
      (node (ref "C21") (pin "1") (pinfunction "1_1") (pintype "passive"))
      (node (ref "C22") (pin "1") (pinfunction "1_1") (pintype "passive"))
      (node (ref "C33") (pin "1") (pinfunction "1_1") (pintype "passive"))
      (node (ref "C34") (pin "1") (pinfunction "1_1") (pintype "passive"))
      (node (ref "C36") (pin "1") (pinfunction "1_1") (pintype "passive"))
      (node (ref "C38") (pin "1") (pinfunction "1_1") (pintype "passive"))
      (node (ref "C39") (pin "1") (pinfunction "1_1") (pintype "passive"))
      (node (ref "C7") (pin "1") (pinfunction "1_1") (pintype "passive"))
      (node (ref "C9") (pin "+") (pinfunction "+_+") (pintype "passive"))
      (node (ref "IC10") (pin "19") (pinfunction "VDD_4_19") (pintype "power_in"))
      (node (ref "IC10") (pin "32") (pinfunction "VDD_1_32") (pintype "power_in"))
      (node (ref "IC10") (pin "48") (pinfunction "VDD_2_48") (pintype "power_in"))
      (node (ref "IC10") (pin "64") (pinfunction "VDD_3_64") (pintype "power_in"))
      (node (ref "IC12") (pin "1") (pinfunction "DBVDD_1") (pintype "bidirectional"))
      (node (ref "IC12") (pin "27") (pinfunction "DCVDD_27") (pintype "bidirectional"))
      (node (ref "IC4") (pin "2") (pinfunction "VOUT_2") (pintype "output"))
      (node (ref "JP1") (pin "1") (pinfunction "1_1") (pintype "passive"))
      (node (ref "R45") (pin "2") (pinfunction "2_2") (pintype "passive"))
      (node (ref "R52") (pin "2") (pinfunction "2_2") (pintype "passive"))
      (node (ref "R53") (pin "2") (pinfunction "2_2") (pintype "passive"))
      (node (ref "SW3") (pin "B") (pinfunction "S_B") (pintype "passive"))
      (node (ref "SW3") (pin "B'") (pinfunction "S1_B'") (pintype "passive"))
    )
    (net (code "2") (name "+3V3_A") (class "Default")
      (node (ref "C10") (pin "+") (pinfunction "+_+") (pintype "passive"))
      (node (ref "C13") (pin "1") (pinfunction "1_1") (pintype "passive"))
      (node (ref "C16") (pin "1") (pinfunction "1_1") (pintype "passive"))
      (node (ref "C17") (pin "1") (pinfunction "1_1") (pintype "passive"))
      (node (ref "C18") (pin "1") (pinfunction "1_1") (pintype "passive"))
      (node (ref "C23") (pin "1") (pinfunction "1_1") (pintype "passive"))
      (node (ref "C29") (pin "1") (pinfunction "1_1") (pintype "passive"))
      (node (ref "C32") (pin "1") (pinfunction "1_1") (pintype "passive"))
      (node (ref "C37") (pin "1") (pinfunction "1_1") (pintype "passive"))
      (node (ref "C46") (pin "1") (pinfunction "1_1") (pintype "passive"))
      (node (ref "C48") (pin "1") (pinfunction "1_1") (pintype "passive"))
      (node (ref "C51") (pin "1") (pinfunction "1_1") (pintype "passive"))
      (node (ref "C6") (pin "1") (pinfunction "1_1") (pintype "passive"))
      (node (ref "C8") (pin "1") (pinfunction "1_1") (pintype "passive"))
      (node (ref "IC10") (pin "13") (pinfunction "VDDA_13") (pintype "power_in"))
      (node (ref "IC11") (pin "16") (pinfunction "VCC_16") (pintype "power_in"))
      (node (ref "IC12") (pin "14") (pinfunction "AVDD_14") (pintype "bidirectional"))
      (node (ref "IC12") (pin "8") (pinfunction "HPVDD_8") (pintype "bidirectional"))
      (node (ref "IC13") (pin "4") (pinfunction "V+_4") (pintype "power_in"))
      (node (ref "IC2") (pin "2") (pinfunction "VOUT_2") (pintype "output"))
      (node (ref "IC3") (pin "16") (pinfunction "VCC_16") (pintype "power_in"))
      (node (ref "IC5") (pin "16") (pinfunction "VCC_16") (pintype "power_in"))
      (node (ref "IC6") (pin "4") (pinfunction "V+_4") (pintype "power_in"))
      (node (ref "IC7") (pin "4") (pinfunction "V+_4") (pintype "power_in"))
      (node (ref "IC8") (pin "16") (pinfunction "VCC_16") (pintype "power_in"))
      (node (ref "IC9") (pin "8") (pinfunction "V+_8") (pintype "power_in"))
      (node (ref "R23") (pin "P$1") (pinfunction "E_P$1") (pintype "passive"))
      (node (ref "R24") (pin "P$1") (pinfunction "E_P$1") (pintype "passive"))
      (node (ref "R25") (pin "P$1") (pinfunction "E_P$1") (pintype "passive"))
      (node (ref "R26") (pin "P$1") (pinfunction "E_P$1") (pintype "passive"))
      (node (ref "R3") (pin "P$1") (pinfunction "E_P$1") (pintype "passive"))
      (node (ref "R4") (pin "P$1") (pinfunction "E_P$1") (pintype "passive"))
      (node (ref "R5") (pin "P$1") (pinfunction "E_P$1") (pintype "passive"))
      (node (ref "R6") (pin "P$1") (pinfunction "E_P$1") (pintype "passive"))
      (node (ref "R60") (pin "2") (pinfunction "2_2") (pintype "passive"))
      (node (ref "R61") (pin "P$1") (pinfunction "E_P$1") (pintype "passive"))
      (node (ref "R62") (pin "P$1") (pinfunction "E_P$1") (pintype "passive"))
      (node (ref "R63") (pin "P$1") (pinfunction "E_P$1") (pintype "passive"))
      (node (ref "R64") (pin "P$1") (pinfunction "E_P$1") (pintype "passive"))
      (node (ref "R65") (pin "P$1") (pinfunction "E_P$1") (pintype "passive"))
      (node (ref "R66") (pin "P$1") (pinfunction "E_P$1") (pintype "passive"))
      (node (ref "R7") (pin "P$1") (pinfunction "E_P$1") (pintype "passive"))
      (node (ref "R76") (pin "P$1") (pinfunction "E_P$1") (pintype "passive"))
      (node (ref "R77") (pin "P$1") (pinfunction "E_P$1") (pintype "passive"))
      (node (ref "R78") (pin "P$1") (pinfunction "E_P$1") (pintype "passive"))
      (node (ref "R79") (pin "P$1") (pinfunction "E_P$1") (pintype "passive"))
      (node (ref "R8") (pin "P$1") (pinfunction "E_P$1") (pintype "passive"))
      (node (ref "R80") (pin "P$1") (pinfunction "E_P$1") (pintype "passive"))
      (node (ref "R81") (pin "P$1") (pinfunction "E_P$1") (pintype "passive"))
      (node (ref "R82") (pin "P$1") (pinfunction "E_P$1") (pintype "passive"))
      (node (ref "R83") (pin "P$1") (pinfunction "E_P$1") (pintype "passive"))
      (node (ref "R84") (pin "P$1") (pinfunction "E_P$1") (pintype "passive"))
      (node (ref "R85") (pin "P$1") (pinfunction "E_P$1") (pintype "passive"))
      (node (ref "R9") (pin "P$1") (pinfunction "E_P$1") (pintype "passive"))
    )
    (net (code "3") (name "ADC_ADDR_0") (class "Default")
      (node (ref "IC10") (pin "4") (pinfunction "PC15/OSC_OUT_4") (pintype "bidirectional"))
      (node (ref "IC11") (pin "11") (pinfunction "A_11") (pintype "input"))
      (node (ref "IC3") (pin "11") (pinfunction "A_11") (pintype "input"))
      (node (ref "IC5") (pin "11") (pinfunction "A_11") (pintype "input"))
      (node (ref "IC8") (pin "11") (pinfunction "A_11") (pintype "input"))
    )
    (net (code "4") (name "ADC_ADDR_1") (class "Default")
      (node (ref "IC10") (pin "3") (pinfunction "PC14/OSC32_IN_3") (pintype "bidirectional"))
      (node (ref "IC11") (pin "10") (pinfunction "B_10") (pintype "input"))
      (node (ref "IC3") (pin "10") (pinfunction "B_10") (pintype "input"))
      (node (ref "IC5") (pin "10") (pinfunction "B_10") (pintype "input"))
      (node (ref "IC8") (pin "10") (pinfunction "B_10") (pintype "input"))
    )
    (net (code "5") (name "ADC_ADDR_2") (class "Default")
      (node (ref "IC10") (pin "2") (pinfunction "PC13-TAMPER-RTC_2") (pintype "bidirectional"))
      (node (ref "IC11") (pin "9") (pinfunction "C_9") (pintype "input"))
      (node (ref "IC3") (pin "9") (pinfunction "C_9") (pintype "input"))
      (node (ref "IC5") (pin "9") (pinfunction "C_9") (pintype "input"))
      (node (ref "IC8") (pin "9") (pinfunction "C_9") (pintype "input"))
    )
    (net (code "6") (name "ADC_BANK_0") (class "Default")
      (node (ref "IC10") (pin "57") (pinfunction "PB5/I2C1_SMBA/SPI1_MOSI/SPI3_MOSI/I2S3_SD_57") (pintype "bidirectional"))
      (node (ref "IC11") (pin "6") (pinfunction "INH_6") (pintype "input"))
    )
    (net (code "7") (name "ADC_BANK_1") (class "Default")
      (node (ref "IC10") (pin "58") (pinfunction "PB6/I2C1_SCL/TIM4_CH1/USART1_TX_58") (pintype "bidirectional"))
      (node (ref "IC8") (pin "6") (pinfunction "INH_6") (pintype "input"))
    )
    (net (code "8") (name "ADC_BANK_2") (class "Default")
      (node (ref "IC10") (pin "59") (pinfunction "PB7/I2C1_SDA/TIM4_CH2/USART1_RX_59") (pintype "bidirectional"))
      (node (ref "IC5") (pin "6") (pinfunction "INH_6") (pintype "input"))
    )
    (net (code "9") (name "ADC_BANK_3") (class "Default")
      (node (ref "IC10") (pin "61") (pinfunction "PB8/TIM4_CH3/I2C1_SCL_61") (pintype "bidirectional"))
      (node (ref "IC3") (pin "6") (pinfunction "INH_6") (pintype "input"))
    )
    (net (code "10") (name "ADC_BLOW_SHAPE") (class "Default")
      (node (ref "C15") (pin "2") (pinfunction "2_2") (pintype "passive"))
      (node (ref "IC10") (pin "16") (pinfunction "PA2/USART2_TX/ADC2/TIM2_CH3_16") (pintype "bidirectional"))
      (node (ref "IC6") (pin "8") (pinfunction "OUT_8") (pintype "output"))
      (node (ref "R12") (pin "1") (pinfunction "1_1") (pintype "passive"))
    )
    (net (code "11") (name "ADC_BLOW_TIMBRE") (class "Default")
      (node (ref "C27") (pin "2") (pinfunction "2_2") (pintype "passive"))
      (node (ref "IC10") (pin "17") (pinfunction "PA3/USART2_RX/ADC3/TIM2_CH4_17") (pintype "bidirectional"))
      (node (ref "IC6") (pin "7") (pinfunction "OUT_7") (pintype "output"))
      (node (ref "R35") (pin "1") (pinfunction "1_1") (pintype "passive"))
    )
    (net (code "12") (name "ADC_BOW_TIMBRE") (class "Default")
      (node (ref "C14") (pin "2") (pinfunction "2_2") (pintype "passive"))
      (node (ref "IC10") (pin "15") (pinfunction "PA1/USART2_RTS/UART4_RX/ADC1/TIM2_CH2_15") (pintype "bidirectional"))
      (node (ref "IC6") (pin "14") (pinfunction "OUT_14") (pintype "output"))
      (node (ref "R11") (pin "1") (pinfunction "1_1") (pintype "passive"))
    )
    (net (code "13") (name "ADC_BRIGHTNESS") (class "Default")
      (node (ref "C42") (pin "2") (pinfunction "2_2") (pintype "passive"))
      (node (ref "IC10") (pin "26") (pinfunction "PB0/ADC8/TIM3_CH3_26") (pintype "bidirectional"))
      (node (ref "IC13") (pin "8") (pinfunction "OUT_8") (pintype "output"))
      (node (ref "R49") (pin "1") (pinfunction "1_1") (pintype "passive"))
    )
    (net (code "14") (name "ADC_DAMPING") (class "Default")
      (node (ref "C20") (pin "2") (pinfunction "2_2") (pintype "passive"))
      (node (ref "IC10") (pin "22") (pinfunction "PA6/SPI1_MISO/ADC6/TIM3_CH1_22") (pintype "bidirectional"))
      (node (ref "IC7") (pin "8") (pinfunction "OUT_8") (pintype "output"))
      (node (ref "R18") (pin "1") (pinfunction "1_1") (pintype "passive"))
    )
    (net (code "15") (name "ADC_FM") (class "Default")
      (node (ref "C25") (pin "2") (pinfunction "2_2") (pintype "passive"))
      (node (ref "IC10") (pin "11") (pinfunction "PC3/SPI2_MOSI/I2S2_SD/ADC13_11") (pintype "bidirectional"))
      (node (ref "IC9") (pin "7") (pinfunction "OUT_7") (pintype "output"))
      (node (ref "R28") (pin "1") (pinfunction "1_1") (pintype "passive"))
    )
    (net (code "16") (name "ADC_GEOMETRY") (class "Default")
      (node (ref "C28") (pin "2") (pinfunction "2_2") (pintype "passive"))
      (node (ref "IC10") (pin "23") (pinfunction "PA7/SPI1_MOSI/ADC7/TIM3_CH2_23") (pintype "bidirectional"))
      (node (ref "IC7") (pin "7") (pinfunction "OUT_7") (pintype "output"))
      (node (ref "R29") (pin "1") (pinfunction "1_1") (pintype "passive"))
    )
    (net (code "17") (name "ADC_POSITION") (class "Default")
      (node (ref "C41") (pin "2") (pinfunction "2_2") (pintype "passive"))
      (node (ref "IC10") (pin "25") (pinfunction "PC5/ADC15_25") (pintype "bidirectional"))
      (node (ref "IC13") (pin "14") (pinfunction "OUT_14") (pintype "output"))
      (node (ref "R48") (pin "1") (pinfunction "1_1") (pintype "passive"))
    )
    (net (code "18") (name "ADC_POTS") (class "Default")
      (node (ref "IC10") (pin "8") (pinfunction "PC0/ADC10_8") (pintype "bidirectional"))
      (node (ref "IC11") (pin "3") (pinfunction "X_3") (pintype "bidirectional"))
      (node (ref "IC3") (pin "3") (pinfunction "X_3") (pintype "bidirectional"))
      (node (ref "IC5") (pin "3") (pinfunction "X_3") (pintype "bidirectional"))
      (node (ref "IC8") (pin "3") (pinfunction "X_3") (pintype "bidirectional"))
      (node (ref "TP1") (pin "P$1") (pinfunction "1_P$1") (pintype "bidirectional"))
    )
    (net (code "19") (name "ADC_PRESSURE") (class "Default")
      (node (ref "C26") (pin "2") (pinfunction "2_2") (pintype "passive"))
      (node (ref "IC10") (pin "14") (pinfunction "PA0-WKUP/USART2_CTS/UART4_TX/ADC0/TIM2_CH1_ETR_14") (pintype "bidirectional"))
      (node (ref "IC6") (pin "1") (pinfunction "OUT_1") (pintype "output"))
      (node (ref "R34") (pin "1") (pinfunction "1_1") (pintype "passive"))
    )
    (net (code "20") (name "ADC_SPACE") (class "Default")
      (node (ref "C50") (pin "2") (pinfunction "2_2") (pintype "passive"))
      (node (ref "IC10") (pin "27") (pinfunction "PB1/ADC9/TIM3_CH4_27") (pintype "bidirectional"))
      (node (ref "IC13") (pin "7") (pinfunction "OUT_7") (pintype "output"))
      (node (ref "R73") (pin "1") (pinfunction "1_1") (pintype "passive"))
    )
    (net (code "21") (name "ADC_STRIKE_SHAPE") (class "Default")
      (node (ref "C30") (pin "2") (pinfunction "2_2") (pintype "passive"))
      (node (ref "IC10") (pin "20") (pinfunction "PA4/SPI1_NSS/SPI3_NSS/USART2_CK/I2S3_WS/ADC4/DAC1_20") (pintype "bidirectional"))
      (node (ref "IC7") (pin "1") (pinfunction "OUT_1") (pintype "output"))
      (node (ref "R46") (pin "1") (pinfunction "1_1") (pintype "passive"))
    )
    (net (code "22") (name "ADC_STRIKE_TIMBRE") (class "Default")
      (node (ref "C19") (pin "2") (pinfunction "2_2") (pintype "passive"))
      (node (ref "IC10") (pin "21") (pinfunction "PA5/SPI1_SCK/ADC5/DAC2_21") (pintype "bidirectional"))
      (node (ref "IC7") (pin "14") (pinfunction "OUT_14") (pintype "output"))
      (node (ref "R17") (pin "1") (pinfunction "1_1") (pintype "passive"))
    )
    (net (code "23") (name "ADC_V_OCT") (class "Default")
      (node (ref "C24") (pin "2") (pinfunction "2_2") (pintype "passive"))
      (node (ref "IC10") (pin "10") (pinfunction "PC2/SPI2_MISO/ADC12_10") (pintype "bidirectional"))
      (node (ref "IC9") (pin "1") (pinfunction "OUT_1") (pintype "output"))
      (node (ref "R27") (pin "1") (pinfunction "1_1") (pintype "passive"))
    )
    (net (code "24") (name "AREF_-10") (class "Default")
      (node (ref "C2") (pin "1") (pinfunction "1_1") (pintype "passive"))
      (node (ref "IC1") (pin "2") (pinfunction "A_2") (pintype "passive"))
      (node (ref "R1") (pin "2") (pinfunction "2_2") (pintype "passive"))
      (node (ref "R14") (pin "2") (pinfunction "2_2") (pintype "passive"))
      (node (ref "R15") (pin "2") (pinfunction "2_2") (pintype "passive"))
      (node (ref "R2") (pin "2") (pinfunction "2_2") (pintype "passive"))
      (node (ref "R20") (pin "2") (pinfunction "2_2") (pintype "passive"))
      (node (ref "R21") (pin "2") (pinfunction "2_2") (pintype "passive"))
      (node (ref "R31") (pin "2") (pinfunction "2_2") (pintype "passive"))
      (node (ref "R32") (pin "2") (pinfunction "2_2") (pintype "passive"))
      (node (ref "R37") (pin "2") (pinfunction "2_2") (pintype "passive"))
      (node (ref "R38") (pin "2") (pinfunction "2_2") (pintype "passive"))
      (node (ref "R41") (pin "2") (pinfunction "2_2") (pintype "passive"))
      (node (ref "R42") (pin "2") (pinfunction "2_2") (pintype "passive"))
      (node (ref "R55") (pin "2") (pinfunction "2_2") (pintype "passive"))
      (node (ref "R56") (pin "2") (pinfunction "2_2") (pintype "passive"))
      (node (ref "R70") (pin "2") (pinfunction "2_2") (pintype "passive"))
    )
    (net (code "25") (name "BOOT_FLASH") (class "Default")
      (node (ref "IC10") (pin "60") (pinfunction "BOOT0_60") (pintype "bidirectional"))
      (node (ref "R50") (pin "2") (pinfunction "2_2") (pintype "passive"))
      (node (ref "SW3") (pin "A") (pinfunction "P_A") (pintype "passive"))
      (node (ref "SW3") (pin "A'") (pinfunction "P1_A'") (pintype "passive"))
    )
    (net (code "26") (name "GATE") (class "Default")
      (node (ref "IC10") (pin "24") (pinfunction "PC4/ADC14_24") (pintype "bidirectional"))
      (node (ref "Q2") (pin "C") (pinfunction "C_C") (pintype "passive"))
      (node (ref "R60") (pin "1") (pinfunction "1_1") (pintype "passive"))
    )
    (net (code "27") (name "GND") (class "Default")
      (node (ref "C1") (pin "+") (pinfunction "+_+") (pintype "passive"))
      (node (ref "C10") (pin "-") (pinfunction "-_-") (pintype "passive"))
      (node (ref "C11") (pin "1") (pinfunction "1_1") (pintype "passive"))
      (node (ref "C12") (pin "1") (pinfunction "1_1") (pintype "passive"))
      (node (ref "C13") (pin "2") (pinfunction "2_2") (pintype "passive"))
      (node (ref "C16") (pin "2") (pinfunction "2_2") (pintype "passive"))
      (node (ref "C17") (pin "2") (pinfunction "2_2") (pintype "passive"))
      (node (ref "C18") (pin "2") (pinfunction "2_2") (pintype "passive"))
      (node (ref "C2") (pin "2") (pinfunction "2_2") (pintype "passive"))
      (node (ref "C21") (pin "2") (pinfunction "2_2") (pintype "passive"))
      (node (ref "C22") (pin "2") (pinfunction "2_2") (pintype "passive"))
      (node (ref "C23") (pin "2") (pinfunction "2_2") (pintype "passive"))
      (node (ref "C29") (pin "2") (pinfunction "2_2") (pintype "passive"))
      (node (ref "C3") (pin "-") (pinfunction "-_-") (pintype "passive"))
      (node (ref "C31") (pin "2") (pinfunction "2_2") (pintype "passive"))
      (node (ref "C32") (pin "2") (pinfunction "2_2") (pintype "passive"))
      (node (ref "C33") (pin "2") (pinfunction "2_2") (pintype "passive"))
      (node (ref "C34") (pin "2") (pinfunction "2_2") (pintype "passive"))
      (node (ref "C35") (pin "2") (pinfunction "2_2") (pintype "passive"))
      (node (ref "C36") (pin "2") (pinfunction "2_2") (pintype "passive"))
      (node (ref "C37") (pin "2") (pinfunction "2_2") (pintype "passive"))
      (node (ref "C38") (pin "2") (pinfunction "2_2") (pintype "passive"))
      (node (ref "C39") (pin "2") (pinfunction "2_2") (pintype "passive"))
      (node (ref "C4") (pin "2") (pinfunction "2_2") (pintype "passive"))
      (node (ref "C44") (pin "2") (pinfunction "2_2") (pintype "passive"))
      (node (ref "C45") (pin "1") (pinfunction "1_1") (pintype "passive"))
      (node (ref "C46") (pin "2") (pinfunction "2_2") (pintype "passive"))
      (node (ref "C47") (pin "2") (pinfunction "2_2") (pintype "passive"))
      (node (ref "C48") (pin "2") (pinfunction "2_2") (pintype "passive"))
      (node (ref "C5") (pin "2") (pinfunction "2_2") (pintype "passive"))
      (node (ref "C51") (pin "2") (pinfunction "2_2") (pintype "passive"))
      (node (ref "C52") (pin "-") (pinfunction "-_-") (pintype "passive"))
      (node (ref "C54") (pin "2") (pinfunction "2_2") (pintype "passive"))
      (node (ref "C57") (pin "2") (pinfunction "2_2") (pintype "passive"))
      (node (ref "C6") (pin "2") (pinfunction "2_2") (pintype "passive"))
      (node (ref "C7") (pin "2") (pinfunction "2_2") (pintype "passive"))
      (node (ref "C8") (pin "2") (pinfunction "2_2") (pintype "passive"))
      (node (ref "C9") (pin "-") (pinfunction "-_-") (pintype "passive"))
      (node (ref "IC1") (pin "1") (pinfunction "C_1") (pintype "passive"))
      (node (ref "IC10") (pin "12") (pinfunction "VSSA_12") (pintype "power_in"))
      (node (ref "IC10") (pin "18") (pinfunction "VSS_4_18") (pintype "power_in"))
      (node (ref "IC10") (pin "28") (pinfunction "PB2/BOOT1_28") (pintype "bidirectional"))
      (node (ref "IC10") (pin "63") (pinfunction "VSS_3_63") (pintype "power_in"))
      (node (ref "IC11") (pin "12") (pinfunction "X3_12") (pintype "bidirectional"))
      (node (ref "IC11") (pin "7") (pinfunction "VEE_7") (pintype "power_in"))
      (node (ref "IC11") (pin "8") (pinfunction "GND_8") (pintype "power_in"))
      (node (ref "IC12") (pin "11") (pinfunction "HPGND_11") (pintype "bidirectional"))
      (node (ref "IC12") (pin "15") (pinfunction "AGND_15") (pintype "bidirectional"))
      (node (ref "IC12") (pin "21") (pinfunction "MODE_21") (pintype "bidirectional"))
      (node (ref "IC12") (pin "22") (pinfunction "CSB_22") (pintype "bidirectional"))
      (node (ref "IC12") (pin "28") (pinfunction "DGND_28") (pintype "bidirectional"))
      (node (ref "IC13") (pin "10") (pinfunction "+IN_10") (pintype "input"))
      (node (ref "IC13") (pin "11") (pinfunction "V-_11") (pintype "power_in"))
      (node (ref "IC13") (pin "12") (pinfunction "+IN_12") (pintype "input"))
      (node (ref "IC13") (pin "3") (pinfunction "+IN_3") (pintype "input"))
      (node (ref "IC13") (pin "5") (pinfunction "+IN_5") (pintype "input"))
      (node (ref "IC14") (pin "3") (pinfunction "+IN_3") (pintype "input"))
      (node (ref "IC14") (pin "5") (pinfunction "+IN_5") (pintype "input"))
      (node (ref "IC2") (pin "1") (pinfunction "GND_1") (pintype "power_in"))
      (node (ref "IC3") (pin "7") (pinfunction "VEE_7") (pintype "power_in"))
      (node (ref "IC3") (pin "8") (pinfunction "GND_8") (pintype "power_in"))
      (node (ref "IC4") (pin "1") (pinfunction "GND_1") (pintype "power_in"))
      (node (ref "IC5") (pin "7") (pinfunction "VEE_7") (pintype "power_in"))
      (node (ref "IC5") (pin "8") (pinfunction "GND_8") (pintype "power_in"))
      (node (ref "IC6") (pin "10") (pinfunction "+IN_10") (pintype "input"))
      (node (ref "IC6") (pin "11") (pinfunction "V-_11") (pintype "power_in"))
      (node (ref "IC6") (pin "12") (pinfunction "+IN_12") (pintype "input"))
      (node (ref "IC6") (pin "3") (pinfunction "+IN_3") (pintype "input"))
      (node (ref "IC6") (pin "5") (pinfunction "+IN_5") (pintype "input"))
      (node (ref "IC7") (pin "10") (pinfunction "+IN_10") (pintype "input"))
      (node (ref "IC7") (pin "11") (pinfunction "V-_11") (pintype "power_in"))
      (node (ref "IC7") (pin "12") (pinfunction "+IN_12") (pintype "input"))
      (node (ref "IC7") (pin "3") (pinfunction "+IN_3") (pintype "input"))
      (node (ref "IC7") (pin "5") (pinfunction "+IN_5") (pintype "input"))
      (node (ref "IC8") (pin "1") (pinfunction "X4_1") (pintype "bidirectional"))
      (node (ref "IC8") (pin "2") (pinfunction "X6_2") (pintype "bidirectional"))
      (node (ref "IC8") (pin "4") (pinfunction "X7_4") (pintype "bidirectional"))
      (node (ref "IC8") (pin "5") (pinfunction "X5_5") (pintype "bidirectional"))
      (node (ref "IC8") (pin "7") (pinfunction "VEE_7") (pintype "power_in"))
      (node (ref "IC8") (pin "8") (pinfunction "GND_8") (pintype "power_in"))
      (node (ref "IC9") (pin "3") (pinfunction "+IN_3") (pintype "input"))
      (node (ref "IC9") (pin "4") (pinfunction "V-_4") (pintype "power_in"))
      (node (ref "IC9") (pin "5") (pinfunction "+IN_5") (pintype "input"))
      (node (ref "J1") (pin "P1") (pinfunction "1_P1") (pintype "passive"))
      (node (ref "J10") (pin "P1") (pinfunction "1_P1") (pintype "passive"))
      (node (ref "J11") (pin "P1") (pinfunction "1_P1") (pintype "passive"))
      (node (ref "J12") (pin "P1") (pinfunction "1_P1") (pintype "passive"))
      (node (ref "J13") (pin "P1") (pinfunction "1_P1") (pintype "passive"))
      (node (ref "J14") (pin "P1") (pinfunction "1_P1") (pintype "passive"))
      (node (ref "J15") (pin "P1") (pinfunction "1_P1") (pintype "passive"))
      (node (ref "J16") (pin "P1") (pinfunction "1_P1") (pintype "passive"))
      (node (ref "J17") (pin "P1") (pinfunction "1_P1") (pintype "passive"))
      (node (ref "J18") (pin "P1") (pinfunction "1_P1") (pintype "passive"))
      (node (ref "J2") (pin "P1") (pinfunction "1_P1") (pintype "passive"))
      (node (ref "J3") (pin "P1") (pinfunction "1_P1") (pintype "passive"))
      (node (ref "J3") (pin "P2") (pinfunction "2_P2") (pintype "passive"))
      (node (ref "J4") (pin "P1") (pinfunction "1_P1") (pintype "passive"))
      (node (ref "J5") (pin "P1") (pinfunction "1_P1") (pintype "passive"))
      (node (ref "J6") (pin "P1") (pinfunction "1_P1") (pintype "passive"))
      (node (ref "J7") (pin "P1") (pinfunction "1_P1") (pintype "passive"))
      (node (ref "J8") (pin "P1") (pinfunction "1_P1") (pintype "passive"))
      (node (ref "J9") (pin "P1") (pinfunction "1_P1") (pintype "passive"))
      (node (ref "JP1") (pin "3") (pinfunction "3_3") (pintype "passive"))
      (node (ref "JP1") (pin "5") (pinfunction "5_5") (pintype "passive"))
      (node (ref "JP1") (pin "9") (pinfunction "9_9") (pintype "passive"))
      (node (ref "JP2") (pin "1") (pinfunction "1_1") (pintype "passive"))
      (node (ref "JP3") (pin "3") (pinfunction "3_3") (pintype "passive"))
      (node (ref "JP3") (pin "4") (pinfunction "4_4") (pintype "passive"))
      (node (ref "JP3") (pin "5") (pinfunction "5_5") (pintype "passive"))
      (node (ref "JP3") (pin "6") (pinfunction "6_6") (pintype "passive"))
      (node (ref "JP3") (pin "7") (pinfunction "7_7") (pintype "passive"))
      (node (ref "JP3") (pin "8") (pinfunction "8_8") (pintype "passive"))
      (node (ref "LED1") (pin "K") (pinfunction "C_K") (pintype "passive"))
      (node (ref "LED2") (pin "K") (pinfunction "C_K") (pintype "passive"))
      (node (ref "Q2") (pin "E") (pinfunction "E_E") (pintype "passive"))
      (node (ref "R23") (pin "P$3") (pinfunction "A_P$3") (pintype "passive"))
      (node (ref "R24") (pin "P$3") (pinfunction "A_P$3") (pintype "passive"))
      (node (ref "R25") (pin "P$3") (pinfunction "A_P$3") (pintype "passive"))
      (node (ref "R26") (pin "P$3") (pinfunction "A_P$3") (pintype "passive"))
      (node (ref "R3") (pin "P$3") (pinfunction "A_P$3") (pintype "passive"))
      (node (ref "R4") (pin "P$3") (pinfunction "A_P$3") (pintype "passive"))
      (node (ref "R5") (pin "P$3") (pinfunction "A_P$3") (pintype "passive"))
      (node (ref "R50") (pin "1") (pinfunction "1_1") (pintype "passive"))
      (node (ref "R59") (pin "1") (pinfunction "1_1") (pintype "passive"))
      (node (ref "R6") (pin "P$3") (pinfunction "A_P$3") (pintype "passive"))
      (node (ref "R61") (pin "P$3") (pinfunction "A_P$3") (pintype "passive"))
      (node (ref "R62") (pin "P$3") (pinfunction "A_P$3") (pintype "passive"))
      (node (ref "R63") (pin "P$3") (pinfunction "A_P$3") (pintype "passive"))
      (node (ref "R64") (pin "P$3") (pinfunction "A_P$3") (pintype "passive"))
      (node (ref "R65") (pin "P$3") (pinfunction "A_P$3") (pintype "passive"))
      (node (ref "R66") (pin "P$3") (pinfunction "A_P$3") (pintype "passive"))
      (node (ref "R69") (pin "1") (pinfunction "1_1") (pintype "passive"))
      (node (ref "R7") (pin "P$3") (pinfunction "A_P$3") (pintype "passive"))
      (node (ref "R74") (pin "1") (pinfunction "1_1") (pintype "passive"))
      (node (ref "R76") (pin "P$3") (pinfunction "A_P$3") (pintype "passive"))
      (node (ref "R77") (pin "P$3") (pinfunction "A_P$3") (pintype "passive"))
      (node (ref "R78") (pin "P$3") (pinfunction "A_P$3") (pintype "passive"))
      (node (ref "R79") (pin "P$3") (pinfunction "A_P$3") (pintype "passive"))
      (node (ref "R8") (pin "P$3") (pinfunction "A_P$3") (pintype "passive"))
      (node (ref "R80") (pin "P$3") (pinfunction "A_P$3") (pintype "passive"))
      (node (ref "R81") (pin "P$3") (pinfunction "A_P$3") (pintype "passive"))
      (node (ref "R82") (pin "P$3") (pinfunction "A_P$3") (pintype "passive"))
      (node (ref "R83") (pin "P$3") (pinfunction "A_P$3") (pintype "passive"))
      (node (ref "R84") (pin "P$3") (pinfunction "A_P$3") (pintype "passive"))
      (node (ref "R85") (pin "P$3") (pinfunction "A_P$3") (pintype "passive"))
      (node (ref "R87") (pin "1") (pinfunction "1_1") (pintype "passive"))
      (node (ref "R9") (pin "P$3") (pinfunction "A_P$3") (pintype "passive"))
      (node (ref "SW1") (pin "L2") (pinfunction "L2_L2") (pintype "passive"))
      (node (ref "SW1") (pin "P3") (pinfunction "A3_P3") (pintype "passive"))
      (node (ref "SW1") (pin "P6") (pinfunction "B3_P6") (pintype "passive"))
      (node (ref "SW2") (pin "A") (pinfunction "P_A") (pintype "passive"))
      (node (ref "SW2") (pin "A'") (pinfunction "P1_A'") (pintype "passive"))
    )
    (net (code "28") (name "I2C_SCL") (class "Default")
      (node (ref "IC10") (pin "29") (pinfunction "PB10/SPI2_SCK/I2S_SCK/I2C2_SCL/USART3_TX_29") (pintype "bidirectional"))
      (node (ref "IC12") (pin "24") (pinfunction "SCLK_24") (pintype "bidirectional"))
      (node (ref "R52") (pin "1") (pinfunction "1_1") (pintype "passive"))
    )
    (net (code "29") (name "I2C_SDA") (class "Default")
      (node (ref "IC10") (pin "30") (pinfunction "PB11/I2C2_SDA/USART3_RX_30") (pintype "bidirectional"))
      (node (ref "IC12") (pin "23") (pinfunction "SDIN_23") (pintype "bidirectional"))
      (node (ref "R53") (pin "1") (pinfunction "1_1") (pintype "passive"))
    )
    (net (code "30") (name "I2S_LRCK") (class "Default")
      (node (ref "IC10") (pin "33") (pinfunction "PB12/SPI2_NSS/I2S2_WS/I2C2_SMBA/USART3_CK/TIM1_BKIN_33") (pintype "bidirectional"))
      (node (ref "IC12") (pin "5") (pinfunction "DACLRC_5") (pintype "bidirectional"))
      (node (ref "IC12") (pin "7") (pinfunction "ADCLRC_7") (pintype "bidirectional"))
    )
    (net (code "31") (name "I2S_MCK") (class "Default")
      (node (ref "IC10") (pin "37") (pinfunction "PC6/I2S2_MCK_37") (pintype "bidirectional"))
      (node (ref "IC12") (pin "25") (pinfunction "XTI/MCLK_25") (pintype "bidirectional"))
    )
    (net (code "32") (name "I2S_SCK") (class "Default")
      (node (ref "IC10") (pin "34") (pinfunction "PB13/SPI2_SCK/I2S2_SCK/USART3_CTS/TIM1_CH1N_34") (pintype "bidirectional"))
      (node (ref "IC12") (pin "3") (pinfunction "BCLK_3") (pintype "bidirectional"))
    )
    (net (code "33") (name "I2S_SIN") (class "Default")
      (node (ref "IC10") (pin "35") (pinfunction "PB14/SPI2_MISO/USART3_RTS/TIM1_CH2N_35") (pintype "bidirectional"))
      (node (ref "IC12") (pin "6") (pinfunction "ADCDAT_6") (pintype "bidirectional"))
    )
    (net (code "34") (name "I2S_SOUT") (class "Default")
      (node (ref "IC10") (pin "36") (pinfunction "PB15/SPI2_MOSI/I2S2_SD/TIM1_CH3N_36") (pintype "bidirectional"))
      (node (ref "IC12") (pin "4") (pinfunction "DACDAT_4") (pintype "bidirectional"))
    )
    (net (code "35") (name "JTCK") (class "Default")
      (node (ref "IC10") (pin "49") (pinfunction "PA14/JTCK-SWCLK_49") (pintype "bidirectional"))
      (node (ref "JP1") (pin "4") (pinfunction "4_4") (pintype "passive"))
    )
    (net (code "36") (name "JTDI") (class "Default")
      (node (ref "IC10") (pin "50") (pinfunction "PA15/JTDI/SPI3_NSS/I2S3_WS_50") (pintype "bidirectional"))
      (node (ref "JP1") (pin "8") (pinfunction "8_8") (pintype "passive"))
    )
    (net (code "37") (name "JTDO") (class "Default")
      (node (ref "IC10") (pin "55") (pinfunction "PB3/JTDO/SPI3_SCK/I2S3_SCK_55") (pintype "bidirectional"))
      (node (ref "JP1") (pin "6") (pinfunction "6_6") (pintype "passive"))
    )
    (net (code "38") (name "JTMS") (class "Default")
      (node (ref "IC10") (pin "46") (pinfunction "PA13/JTMS-SWDAT_46") (pintype "bidirectional"))
      (node (ref "JP1") (pin "2") (pinfunction "2_2") (pintype "passive"))
    )
    (net (code "39") (name "LED_GATE") (class "Default")
      (node (ref "IC10") (pin "38") (pinfunction "PC7/I2S3_MCK_38") (pintype "bidirectional"))
      (node (ref "R10") (pin "1") (pinfunction "1_1") (pintype "passive"))
    )
    (net (code "40") (name "LIN") (class "Default")
      (node (ref "C56") (pin "+") (pinfunction "+_+") (pintype "passive"))
      (node (ref "IC12") (pin "20") (pinfunction "LLINEIN_20") (pintype "bidirectional"))
    )
    (net (code "41") (name "LOUT") (class "Default")
      (node (ref "C40") (pin "+") (pinfunction "+_+") (pintype "passive"))
      (node (ref "IC12") (pin "12") (pinfunction "LOUT_12") (pintype "bidirectional"))
    )
    (net (code "42") (name "Net-(C40-Pad-)") (class "Default")
      (node (ref "C40") (pin "-") (pinfunction "-_-") (pintype "passive"))
      (node (ref "R58") (pin "2") (pinfunction "2_2") (pintype "passive"))
      (node (ref "R59") (pin "2") (pinfunction "2_2") (pintype "passive"))
    )
    (net (code "43") (name "Net-(C53-Pad-)") (class "Default")
      (node (ref "C53") (pin "-") (pinfunction "-_-") (pintype "passive"))
      (node (ref "R68") (pin "2") (pinfunction "2_2") (pintype "passive"))
      (node (ref "R69") (pin "2") (pinfunction "2_2") (pintype "passive"))
    )
    (net (code "44") (name "Net-(C54-Pad1)") (class "Default")
      (node (ref "C54") (pin "1") (pinfunction "1_1") (pintype "passive"))
      (node (ref "C55") (pin "-") (pinfunction "-_-") (pintype "passive"))
      (node (ref "R74") (pin "2") (pinfunction "2_2") (pintype "passive"))
      (node (ref "R75") (pin "1") (pinfunction "1_1") (pintype "passive"))
    )
    (net (code "45") (name "Net-(C56-Pad-)") (class "Default")
      (node (ref "C56") (pin "-") (pinfunction "-_-") (pintype "passive"))
      (node (ref "C57") (pin "1") (pinfunction "1_1") (pintype "passive"))
      (node (ref "R86") (pin "1") (pinfunction "1_1") (pintype "passive"))
      (node (ref "R87") (pin "2") (pinfunction "2_2") (pintype "passive"))
    )
    (net (code "46") (name "Net-(D1-PadA)") (class "Default")
      (node (ref "D1") (pin "A") (pinfunction "A_A") (pintype "passive"))
      (node (ref "JP3") (pin "1") (pinfunction "1_1") (pintype "passive"))
      (node (ref "JP3") (pin "2") (pinfunction "2_2") (pintype "passive"))
    )
    (net (code "47") (name "Net-(D2-PadC)") (class "Default")
      (node (ref "D2") (pin "C") (pinfunction "C_C") (pintype "passive"))
      (node (ref "JP3") (pin "10") (pinfunction "10_10") (pintype "passive"))
      (node (ref "JP3") (pin "9") (pinfunction "9_9") (pintype "passive"))
    )
    (net (code "48") (name "Net-(IC2-VIN)") (class "Default")
      (node (ref "C4") (pin "1") (pinfunction "1_1") (pintype "passive"))
      (node (ref "IC2") (pin "3") (pinfunction "VIN_3") (pintype "input"))
      (node (ref "L2") (pin "2") (pinfunction "2_2") (pintype "passive"))
    )
    (net (code "49") (name "Net-(IC3A-X0)") (class "Default")
      (node (ref "IC3") (pin "13") (pinfunction "X0_13") (pintype "bidirectional"))
      (node (ref "R26") (pin "P$2") (pinfunction "S_P$2") (pintype "passive"))
    )
    (net (code "50") (name "Net-(IC3A-X1)") (class "Default")
      (node (ref "IC3") (pin "14") (pinfunction "X1_14") (pintype "bidirectional"))
      (node (ref "R9") (pin "P$2") (pinfunction "S_P$2") (pintype "passive"))
    )
    (net (code "51") (name "Net-(IC3A-X2)") (class "Default")
      (node (ref "IC3") (pin "15") (pinfunction "X2_15") (pintype "bidirectional"))
      (node (ref "R8") (pin "P$2") (pinfunction "S_P$2") (pintype "passive"))
    )
    (net (code "52") (name "Net-(IC3A-X3)") (class "Default")
      (node (ref "IC3") (pin "12") (pinfunction "X3_12") (pintype "bidirectional"))
      (node (ref "R66") (pin "P$2") (pinfunction "S_P$2") (pintype "passive"))
    )
    (net (code "53") (name "Net-(IC3A-X4)") (class "Default")
      (node (ref "IC3") (pin "1") (pinfunction "X4_1") (pintype "bidirectional"))
      (node (ref "R3") (pin "P$2") (pinfunction "S_P$2") (pintype "passive"))
    )
    (net (code "54") (name "Net-(IC3A-X5)") (class "Default")
      (node (ref "IC3") (pin "5") (pinfunction "X5_5") (pintype "bidirectional"))
      (node (ref "R5") (pin "P$2") (pinfunction "S_P$2") (pintype "passive"))
    )
    (net (code "55") (name "Net-(IC3A-X6)") (class "Default")
      (node (ref "IC3") (pin "2") (pinfunction "X6_2") (pintype "bidirectional"))
      (node (ref "R4") (pin "P$2") (pinfunction "S_P$2") (pintype "passive"))
    )
    (net (code "56") (name "Net-(IC3A-X7)") (class "Default")
      (node (ref "IC3") (pin "4") (pinfunction "X7_4") (pintype "bidirectional"))
      (node (ref "R25") (pin "P$2") (pinfunction "S_P$2") (pintype "passive"))
    )
    (net (code "57") (name "Net-(IC4-VIN)") (class "Default")
      (node (ref "C5") (pin "1") (pinfunction "1_1") (pintype "passive"))
      (node (ref "IC4") (pin "3") (pinfunction "VIN_3") (pintype "input"))
      (node (ref "L1") (pin "2") (pinfunction "2_2") (pintype "passive"))
    )
    (net (code "58") (name "Net-(IC5A-X0)") (class "Default")
      (node (ref "IC5") (pin "13") (pinfunction "X0_13") (pintype "bidirectional"))
      (node (ref "R83") (pin "P$2") (pinfunction "S_P$2") (pintype "passive"))
    )
    (net (code "59") (name "Net-(IC5A-X1)") (class "Default")
      (node (ref "IC5") (pin "14") (pinfunction "X1_14") (pintype "bidirectional"))
      (node (ref "R84") (pin "P$2") (pinfunction "S_P$2") (pintype "passive"))
    )
    (net (code "60") (name "Net-(IC5A-X2)") (class "Default")
      (node (ref "IC5") (pin "15") (pinfunction "X2_15") (pintype "bidirectional"))
      (node (ref "R85") (pin "P$2") (pinfunction "S_P$2") (pintype "passive"))
    )
    (net (code "61") (name "Net-(IC5A-X3)") (class "Default")
      (node (ref "IC5") (pin "12") (pinfunction "X3_12") (pintype "bidirectional"))
      (node (ref "R82") (pin "P$2") (pinfunction "S_P$2") (pintype "passive"))
    )
    (net (code "62") (name "Net-(IC5A-X4)") (class "Default")
      (node (ref "IC5") (pin "1") (pinfunction "X4_1") (pintype "bidirectional"))
      (node (ref "R23") (pin "P$2") (pinfunction "S_P$2") (pintype "passive"))
    )
    (net (code "63") (name "Net-(IC5A-X5)") (class "Default")
      (node (ref "IC5") (pin "5") (pinfunction "X5_5") (pintype "bidirectional"))
      (node (ref "R24") (pin "P$2") (pinfunction "S_P$2") (pintype "passive"))
    )
    (net (code "64") (name "Net-(IC5A-X6)") (class "Default")
      (node (ref "IC5") (pin "2") (pinfunction "X6_2") (pintype "bidirectional"))
      (node (ref "R6") (pin "P$2") (pinfunction "S_P$2") (pintype "passive"))
    )
    (net (code "65") (name "Net-(IC5A-X7)") (class "Default")
      (node (ref "IC5") (pin "4") (pinfunction "X7_4") (pintype "bidirectional"))
      (node (ref "R7") (pin "P$2") (pinfunction "S_P$2") (pintype "passive"))
    )
    (net (code "66") (name "Net-(IC6A--IN)") (class "Default")
      (node (ref "C26") (pin "1") (pinfunction "1_1") (pintype "passive"))
      (node (ref "IC6") (pin "2") (pinfunction "-IN_2") (pintype "input"))
      (node (ref "R30") (pin "1") (pinfunction "1_1") (pintype "passive"))
      (node (ref "R31") (pin "1") (pinfunction "1_1") (pintype "passive"))
      (node (ref "R34") (pin "2") (pinfunction "2_2") (pintype "passive"))
    )
    (net (code "67") (name "Net-(IC6B--IN)") (class "Default")
      (node (ref "C27") (pin "1") (pinfunction "1_1") (pintype "passive"))
      (node (ref "IC6") (pin "6") (pinfunction "-IN_6") (pintype "input"))
      (node (ref "R32") (pin "1") (pinfunction "1_1") (pintype "passive"))
      (node (ref "R33") (pin "1") (pinfunction "1_1") (pintype "passive"))
      (node (ref "R35") (pin "2") (pinfunction "2_2") (pintype "passive"))
    )
    (net (code "68") (name "Net-(IC6C--IN)") (class "Default")
      (node (ref "C15") (pin "1") (pinfunction "1_1") (pintype "passive"))
      (node (ref "IC6") (pin "9") (pinfunction "-IN_9") (pintype "input"))
      (node (ref "R12") (pin "2") (pinfunction "2_2") (pintype "passive"))
      (node (ref "R15") (pin "1") (pinfunction "1_1") (pintype "passive"))
      (node (ref "R16") (pin "1") (pinfunction "1_1") (pintype "passive"))
    )
    (net (code "69") (name "Net-(IC6D--IN)") (class "Default")
      (node (ref "C14") (pin "1") (pinfunction "1_1") (pintype "passive"))
      (node (ref "IC6") (pin "13") (pinfunction "-IN_13") (pintype "input"))
      (node (ref "R11") (pin "2") (pinfunction "2_2") (pintype "passive"))
      (node (ref "R13") (pin "1") (pinfunction "1_1") (pintype "passive"))
      (node (ref "R14") (pin "1") (pinfunction "1_1") (pintype "passive"))
    )
    (net (code "70") (name "Net-(IC7A--IN)") (class "Default")
      (node (ref "C30") (pin "1") (pinfunction "1_1") (pintype "passive"))
      (node (ref "IC7") (pin "2") (pinfunction "-IN_2") (pintype "input"))
      (node (ref "R40") (pin "1") (pinfunction "1_1") (pintype "passive"))
      (node (ref "R41") (pin "1") (pinfunction "1_1") (pintype "passive"))
      (node (ref "R46") (pin "2") (pinfunction "2_2") (pintype "passive"))
    )
    (net (code "71") (name "Net-(IC7B--IN)") (class "Default")
      (node (ref "C28") (pin "1") (pinfunction "1_1") (pintype "passive"))
      (node (ref "IC7") (pin "6") (pinfunction "-IN_6") (pintype "input"))
      (node (ref "R29") (pin "2") (pinfunction "2_2") (pintype "passive"))
      (node (ref "R42") (pin "1") (pinfunction "1_1") (pintype "passive"))
      (node (ref "R43") (pin "1") (pinfunction "1_1") (pintype "passive"))
    )
    (net (code "72") (name "Net-(IC7C--IN)") (class "Default")
      (node (ref "C20") (pin "1") (pinfunction "1_1") (pintype "passive"))
      (node (ref "IC7") (pin "9") (pinfunction "-IN_9") (pintype "input"))
      (node (ref "R18") (pin "2") (pinfunction "2_2") (pintype "passive"))
      (node (ref "R21") (pin "1") (pinfunction "1_1") (pintype "passive"))
      (node (ref "R22") (pin "1") (pinfunction "1_1") (pintype "passive"))
    )
    (net (code "73") (name "Net-(IC7D--IN)") (class "Default")
      (node (ref "C19") (pin "1") (pinfunction "1_1") (pintype "passive"))
      (node (ref "IC7") (pin "13") (pinfunction "-IN_13") (pintype "input"))
      (node (ref "R17") (pin "2") (pinfunction "2_2") (pintype "passive"))
      (node (ref "R19") (pin "1") (pinfunction "1_1") (pintype "passive"))
      (node (ref "R20") (pin "1") (pinfunction "1_1") (pintype "passive"))
    )
    (net (code "74") (name "Net-(IC8A-X0)") (class "Default")
      (node (ref "IC8") (pin "13") (pinfunction "X0_13") (pintype "bidirectional"))
      (node (ref "R79") (pin "P$2") (pinfunction "S_P$2") (pintype "passive"))
    )
    (net (code "75") (name "Net-(IC8A-X1)") (class "Default")
      (node (ref "IC8") (pin "14") (pinfunction "X1_14") (pintype "bidirectional"))
      (node (ref "R80") (pin "P$2") (pinfunction "S_P$2") (pintype "passive"))
    )
    (net (code "76") (name "Net-(IC8A-X2)") (class "Default")
      (node (ref "IC8") (pin "15") (pinfunction "X2_15") (pintype "bidirectional"))
      (node (ref "R81") (pin "P$2") (pinfunction "S_P$2") (pintype "passive"))
    )
    (net (code "77") (name "Net-(IC8A-X3)") (class "Default")
      (node (ref "IC8") (pin "12") (pinfunction "X3_12") (pintype "bidirectional"))
      (node (ref "R78") (pin "P$2") (pinfunction "S_P$2") (pintype "passive"))
    )
    (net (code "78") (name "Net-(IC9A--IN)") (class "Default")
      (node (ref "C24") (pin "1") (pinfunction "1_1") (pintype "passive"))
      (node (ref "IC9") (pin "2") (pinfunction "-IN_2") (pintype "input"))
      (node (ref "R27") (pin "2") (pinfunction "2_2") (pintype "passive"))
      (node (ref "R36") (pin "1") (pinfunction "1_1") (pintype "passive"))
      (node (ref "R37") (pin "1") (pinfunction "1_1") (pintype "passive"))
    )
    (net (code "79") (name "Net-(IC9B--IN)") (class "Default")
      (node (ref "C25") (pin "1") (pinfunction "1_1") (pintype "passive"))
      (node (ref "IC9") (pin "6") (pinfunction "-IN_6") (pintype "input"))
      (node (ref "R28") (pin "2") (pinfunction "2_2") (pintype "passive"))
      (node (ref "R38") (pin "1") (pinfunction "1_1") (pintype "passive"))
      (node (ref "R39") (pin "1") (pinfunction "1_1") (pintype "passive"))
    )
    (net (code "80") (name "Net-(IC10-PA8{slash}USART1_CK{slash}TIM1_CH1{slash}MCO)") (class "Default")
      (node (ref "IC10") (pin "41") (pinfunction "PA8/USART1_CK/TIM1_CH1/MCO_41") (pintype "bidirectional"))
      (node (ref "R47") (pin "1") (pinfunction "1_1") (pintype "passive"))
    )
    (net (code "81") (name "Net-(IC10-PA11{slash}USART1_CTS{slash}CANRX{slash}USBDM{slash}TIM1_CH4)") (class "Default")
      (node (ref "IC10") (pin "44") (pinfunction "PA11/USART1_CTS/CANRX/USBDM/TIM1_CH4_44") (pintype "bidirectional"))
      (node (ref "R44") (pin "1") (pinfunction "1_1") (pintype "passive"))
    )
    (net (code "82") (name "Net-(IC10-PD0{slash}OSC_IN)") (class "Default")
      (node (ref "C12") (pin "2") (pinfunction "2_2") (pintype "passive"))
      (node (ref "IC10") (pin "5") (pinfunction "PD0/OSC_IN_5") (pintype "bidirectional"))
      (node (ref "Q1") (pin "2") (pinfunction "2_2") (pintype "passive"))
    )
    (net (code "83") (name "Net-(IC10-PD1{slash}OSC_OUT)") (class "Default")
      (node (ref "C11") (pin "2") (pinfunction "2_2") (pintype "passive"))
      (node (ref "IC10") (pin "6") (pinfunction "PD1/OSC_OUT_6") (pintype "bidirectional"))
      (node (ref "Q1") (pin "1") (pinfunction "1_1") (pintype "passive"))
    )
    (net (code "84") (name "Net-(IC10-VCAP_1)") (class "Default")
      (node (ref "C31") (pin "1") (pinfunction "1_1") (pintype "passive"))
      (node (ref "IC10") (pin "31") (pinfunction "VCAP_1_31") (pintype "power_in"))
    )
    (net (code "85") (name "Net-(IC10-VCAP_2)") (class "Default")
      (node (ref "C35") (pin "1") (pinfunction "1_1") (pintype "passive"))
      (node (ref "IC10") (pin "47") (pinfunction "VCAP_2_47") (pintype "power_in"))
    )
    (net (code "86") (name "Net-(IC11A-X0)") (class "Default")
      (node (ref "IC11") (pin "13") (pinfunction "X0_13") (pintype "bidirectional"))
      (node (ref "R65") (pin "P$2") (pinfunction "S_P$2") (pintype "passive"))
    )
    (net (code "87") (name "Net-(IC11A-X1)") (class "Default")
      (node (ref "IC11") (pin "14") (pinfunction "X1_14") (pintype "bidirectional"))
      (node (ref "R76") (pin "P$2") (pinfunction "S_P$2") (pintype "passive"))
    )
    (net (code "88") (name "Net-(IC11A-X2)") (class "Default")
      (node (ref "IC11") (pin "15") (pinfunction "X2_15") (pintype "bidirectional"))
      (node (ref "R77") (pin "P$2") (pinfunction "S_P$2") (pintype "passive"))
    )
    (net (code "89") (name "Net-(IC11A-X4)") (class "Default")
      (node (ref "IC11") (pin "1") (pinfunction "X4_1") (pintype "bidirectional"))
      (node (ref "R64") (pin "P$2") (pinfunction "S_P$2") (pintype "passive"))
    )
    (net (code "90") (name "Net-(IC11A-X5)") (class "Default")
      (node (ref "IC11") (pin "5") (pinfunction "X5_5") (pintype "bidirectional"))
      (node (ref "R61") (pin "P$2") (pinfunction "S_P$2") (pintype "passive"))
    )
    (net (code "91") (name "Net-(IC11A-X6)") (class "Default")
      (node (ref "IC11") (pin "2") (pinfunction "X6_2") (pintype "bidirectional"))
      (node (ref "R63") (pin "P$2") (pinfunction "S_P$2") (pintype "passive"))
    )
    (net (code "92") (name "Net-(IC11A-X7)") (class "Default")
      (node (ref "IC11") (pin "4") (pinfunction "X7_4") (pintype "bidirectional"))
      (node (ref "R62") (pin "P$2") (pinfunction "S_P$2") (pintype "passive"))
    )
    (net (code "93") (name "Net-(IC12-VMID)") (class "Default")
      (node (ref "C47") (pin "1") (pinfunction "1_1") (pintype "passive"))
      (node (ref "C52") (pin "+") (pinfunction "+_+") (pintype "passive"))
      (node (ref "IC12") (pin "16") (pinfunction "VMID_16") (pintype "bidirectional"))
    )
    (net (code "94") (name "Net-(IC13A--IN)") (class "Default")
      (node (ref "IC13") (pin "1") (pinfunction "OUT_1") (pintype "output"))
      (node (ref "IC13") (pin "2") (pinfunction "-IN_2") (pintype "input"))
    )
    (net (code "95") (name "Net-(IC13B--IN)") (class "Default")
      (node (ref "C50") (pin "1") (pinfunction "1_1") (pintype "passive"))
      (node (ref "IC13") (pin "6") (pinfunction "-IN_6") (pintype "input"))
      (node (ref "R70") (pin "1") (pinfunction "1_1") (pintype "passive"))
      (node (ref "R71") (pin "1") (pinfunction "1_1") (pintype "passive"))
      (node (ref "R73") (pin "2") (pinfunction "2_2") (pintype "passive"))
    )
    (net (code "96") (name "Net-(IC13C--IN)") (class "Default")
      (node (ref "C42") (pin "1") (pinfunction "1_1") (pintype "passive"))
      (node (ref "IC13") (pin "9") (pinfunction "-IN_9") (pintype "input"))
      (node (ref "R49") (pin "2") (pinfunction "2_2") (pintype "passive"))
      (node (ref "R56") (pin "1") (pinfunction "1_1") (pintype "passive"))
      (node (ref "R57") (pin "1") (pinfunction "1_1") (pintype "passive"))
    )
    (net (code "97") (name "Net-(IC13D--IN)") (class "Default")
      (node (ref "C41") (pin "1") (pinfunction "1_1") (pintype "passive"))
      (node (ref "IC13") (pin "13") (pinfunction "-IN_13") (pintype "input"))
      (node (ref "R48") (pin "2") (pinfunction "2_2") (pintype "passive"))
      (node (ref "R54") (pin "1") (pinfunction "1_1") (pintype "passive"))
      (node (ref "R55") (pin "1") (pinfunction "1_1") (pintype "passive"))
    )
    (net (code "98") (name "Net-(IC14A--IN)") (class "Default")
      (node (ref "C49") (pin "1") (pinfunction "1_1") (pintype "passive"))
      (node (ref "IC14") (pin "2") (pinfunction "-IN_2") (pintype "input"))
      (node (ref "R68") (pin "1") (pinfunction "1_1") (pintype "passive"))
      (node (ref "R72") (pin "2") (pinfunction "2_2") (pintype "passive"))
    )
    (net (code "99") (name "Net-(IC14A-OUT)") (class "Default")
      (node (ref "C49") (pin "2") (pinfunction "2_2") (pintype "passive"))
      (node (ref "IC14") (pin "1") (pinfunction "OUT_1") (pintype "output"))
      (node (ref "R72") (pin "1") (pinfunction "1_1") (pintype "passive"))
      (node (ref "R89") (pin "2") (pinfunction "2_2") (pintype "passive"))
    )
    (net (code "100") (name "Net-(IC14B--IN)") (class "Default")
      (node (ref "C43") (pin "1") (pinfunction "1_1") (pintype "passive"))
      (node (ref "IC14") (pin "6") (pinfunction "-IN_6") (pintype "input"))
      (node (ref "R51") (pin "2") (pinfunction "2_2") (pintype "passive"))
      (node (ref "R58") (pin "1") (pinfunction "1_1") (pintype "passive"))
    )
    (net (code "101") (name "Net-(IC14B-OUT)") (class "Default")
      (node (ref "C43") (pin "2") (pinfunction "2_2") (pintype "passive"))
      (node (ref "IC14") (pin "7") (pinfunction "OUT_7") (pintype "output"))
      (node (ref "R51") (pin "1") (pinfunction "1_1") (pintype "passive"))
      (node (ref "R88") (pin "2") (pinfunction "2_2") (pintype "passive"))
    )
    (net (code "102") (name "Net-(J1-3)") (class "Default")
      (node (ref "J1") (pin "P3") (pinfunction "3_P3") (pintype "passive"))
      (node (ref "R36") (pin "2") (pinfunction "2_2") (pintype "passive"))
    )
    (net (code "103") (name "Net-(J2-3)") (class "Default")
      (node (ref "J2") (pin "P3") (pinfunction "3_P3") (pintype "passive"))
      (node (ref "R39") (pin "2") (pinfunction "2_2") (pintype "passive"))
    )
    (net (code "104") (name "Net-(J3-3)") (class "Default")
      (node (ref "J3") (pin "P3") (pinfunction "3_P3") (pintype "passive"))
      (node (ref "R67") (pin "1") (pinfunction "1_1") (pintype "passive"))
    )
    (net (code "105") (name "Net-(J4-3)") (class "Default")
      (node (ref "J4") (pin "P3") (pinfunction "3_P3") (pintype "passive"))
      (node (ref "R30") (pin "2") (pinfunction "2_2") (pintype "passive"))
    )
    (net (code "106") (name "Net-(J5-3)") (class "Default")
      (node (ref "J5") (pin "P3") (pinfunction "3_P3") (pintype "passive"))
      (node (ref "R75") (pin "2") (pinfunction "2_2") (pintype "passive"))
    )
    (net (code "107") (name "Net-(J6-3)") (class "Default")
      (node (ref "J6") (pin "P3") (pinfunction "3_P3") (pintype "passive"))
      (node (ref "R86") (pin "2") (pinfunction "2_2") (pintype "passive"))
    )
    (net (code "108") (name "Net-(J7-3)") (class "Default")
      (node (ref "J7") (pin "P3") (pinfunction "3_P3") (pintype "passive"))
      (node (ref "R88") (pin "1") (pinfunction "1_1") (pintype "passive"))
    )
    (net (code "109") (name "Net-(J8-3)") (class "Default")
      (node (ref "J8") (pin "P3") (pinfunction "3_P3") (pintype "passive"))
      (node (ref "R89") (pin "1") (pinfunction "1_1") (pintype "passive"))
    )
    (net (code "110") (name "Net-(J9-3)") (class "Default")
      (node (ref "J9") (pin "P3") (pinfunction "3_P3") (pintype "passive"))
      (node (ref "R13") (pin "2") (pinfunction "2_2") (pintype "passive"))
    )
    (net (code "111") (name "Net-(J10-3)") (class "Default")
      (node (ref "J10") (pin "P3") (pinfunction "3_P3") (pintype "passive"))
      (node (ref "R16") (pin "2") (pinfunction "2_2") (pintype "passive"))
    )
    (net (code "112") (name "Net-(J11-3)") (class "Default")
      (node (ref "J11") (pin "P3") (pinfunction "3_P3") (pintype "passive"))
      (node (ref "R33") (pin "2") (pinfunction "2_2") (pintype "passive"))
    )
    (net (code "113") (name "Net-(J12-3)") (class "Default")
      (node (ref "J12") (pin "P3") (pinfunction "3_P3") (pintype "passive"))
      (node (ref "R40") (pin "2") (pinfunction "2_2") (pintype "passive"))
    )
    (net (code "114") (name "Net-(J13-3)") (class "Default")
      (node (ref "J13") (pin "P3") (pinfunction "3_P3") (pintype "passive"))
      (node (ref "R19") (pin "2") (pinfunction "2_2") (pintype "passive"))
    )
    (net (code "115") (name "Net-(J14-3)") (class "Default")
      (node (ref "J14") (pin "P3") (pinfunction "3_P3") (pintype "passive"))
      (node (ref "R22") (pin "2") (pinfunction "2_2") (pintype "passive"))
    )
    (net (code "116") (name "Net-(J15-3)") (class "Default")
      (node (ref "J15") (pin "P3") (pinfunction "3_P3") (pintype "passive"))
      (node (ref "R43") (pin "2") (pinfunction "2_2") (pintype "passive"))
    )
    (net (code "117") (name "Net-(J16-3)") (class "Default")
      (node (ref "J16") (pin "P3") (pinfunction "3_P3") (pintype "passive"))
      (node (ref "R54") (pin "2") (pinfunction "2_2") (pintype "passive"))
    )
    (net (code "118") (name "Net-(J17-3)") (class "Default")
      (node (ref "J17") (pin "P3") (pinfunction "3_P3") (pintype "passive"))
      (node (ref "R57") (pin "2") (pinfunction "2_2") (pintype "passive"))
    )
    (net (code "119") (name "Net-(J18-3)") (class "Default")
      (node (ref "J18") (pin "P3") (pinfunction "3_P3") (pintype "passive"))
      (node (ref "R71") (pin "2") (pinfunction "2_2") (pintype "passive"))
    )
    (net (code "120") (name "Net-(LED1-PadA)") (class "Default")
      (node (ref "LED1") (pin "A") (pinfunction "A_A") (pintype "passive"))
      (node (ref "R47") (pin "2") (pinfunction "2_2") (pintype "passive"))
    )
    (net (code "121") (name "Net-(LED2-PadA)") (class "Default")
      (node (ref "LED2") (pin "A") (pinfunction "A_A") (pintype "passive"))
      (node (ref "R44") (pin "2") (pinfunction "2_2") (pintype "passive"))
    )
    (net (code "122") (name "Net-(Q2-PadB)") (class "Default")
      (node (ref "Q2") (pin "B") (pinfunction "B_B") (pintype "passive"))
      (node (ref "R67") (pin "2") (pinfunction "2_2") (pintype "passive"))
    )
    (net (code "123") (name "Net-(R10-Pad2)") (class "Default")
      (node (ref "R10") (pin "2") (pinfunction "2_2") (pintype "passive"))
      (node (ref "SW1") (pin "L1") (pinfunction "L1_L1") (pintype "passive"))
    )
    (net (code "124") (name "RESET") (class "Default")
      (node (ref "IC10") (pin "7") (pinfunction "NRST_7") (pintype "bidirectional"))
      (node (ref "JP1") (pin "10") (pinfunction "10_10") (pintype "passive"))
      (node (ref "R45") (pin "1") (pinfunction "1_1") (pintype "passive"))
      (node (ref "SW2") (pin "B") (pinfunction "S_B") (pintype "passive"))
      (node (ref "SW2") (pin "B'") (pinfunction "S1_B'") (pintype "passive"))
    )
    (net (code "125") (name "RIN") (class "Default")
      (node (ref "C55") (pin "+") (pinfunction "+_+") (pintype "passive"))
      (node (ref "IC12") (pin "19") (pinfunction "RLINEIN_19") (pintype "bidirectional"))
    )
    (net (code "126") (name "ROUT") (class "Default")
      (node (ref "C53") (pin "+") (pinfunction "+_+") (pintype "passive"))
      (node (ref "IC12") (pin "13") (pinfunction "ROUT_13") (pintype "bidirectional"))
    )
    (net (code "127") (name "RX") (class "Default")
      (node (ref "IC10") (pin "43") (pinfunction "PA10/USART1_RX/TIM1_CH3_43") (pintype "bidirectional"))
      (node (ref "JP2") (pin "4") (pinfunction "4_4") (pintype "passive"))
    )
    (net (code "128") (name "SW_GATE") (class "Default")
      (node (ref "IC10") (pin "9") (pinfunction "PC1/ADC11_9") (pintype "bidirectional"))
      (node (ref "SW1") (pin "P2") (pinfunction "A2_P2") (pintype "passive"))
      (node (ref "SW1") (pin "P5") (pinfunction "B2_P5") (pintype "passive"))
    )
    (net (code "129") (name "TX") (class "Default")
      (node (ref "IC10") (pin "42") (pinfunction "PA9/USART1_TX/TIM1_CH2_42") (pintype "bidirectional"))
      (node (ref "JP2") (pin "5") (pinfunction "5_5") (pintype "passive"))
    )
    (net (code "130") (name "VBAT") (class "Default")
      (node (ref "IC10") (pin "1") (pinfunction "VBAT_1") (pintype "power_in"))
    )
    (net (code "131") (name "VCC") (class "Default")
      (node (ref "C3") (pin "+") (pinfunction "+_+") (pintype "passive"))
      (node (ref "C44") (pin "1") (pinfunction "1_1") (pintype "passive"))
      (node (ref "D1") (pin "C") (pinfunction "C_C") (pintype "passive"))
      (node (ref "IC14") (pin "8") (pinfunction "V+_8") (pintype "power_in"))
      (node (ref "L1") (pin "1") (pinfunction "1_1") (pintype "passive"))
      (node (ref "L2") (pin "1") (pinfunction "1_1") (pintype "passive"))
    )
    (net (code "132") (name "VEE") (class "Default")
      (node (ref "C1") (pin "-") (pinfunction "-_-") (pintype "passive"))
      (node (ref "C45") (pin "2") (pinfunction "2_2") (pintype "passive"))
      (node (ref "D2") (pin "A") (pinfunction "A_A") (pintype "passive"))
      (node (ref "IC14") (pin "4") (pinfunction "V-_4") (pintype "power_in"))
      (node (ref "R1") (pin "1") (pinfunction "1_1") (pintype "passive"))
      (node (ref "R2") (pin "1") (pinfunction "1_1") (pintype "passive"))
    )
    (net (code "133") (name "unconnected-(IC10-PA12{slash}USART1_RTS{slash}CANTX{slash}USBDP{slash}TIM1_ETR-Pad45)") (class "Default")
      (node (ref "IC10") (pin "45") (pinfunction "PA12/USART1_RTS/CANTX/USBDP/TIM1_ETR_45") (pintype "bidirectional"))
    )
    (net (code "134") (name "unconnected-(IC10-PB4{slash}NJTRST{slash}SPI3_MISO{slash}SPI1_MISO-Pad56)") (class "Default")
      (node (ref "IC10") (pin "56") (pinfunction "PB4/NJTRST/SPI3_MISO/SPI1_MISO_56") (pintype "bidirectional"))
    )
    (net (code "135") (name "unconnected-(IC10-PB9{slash}SPI2_NSS{slash}I2S2_WS{slash}I2C1_SDA{slash}TIM4_CH4-Pad62)") (class "Default")
      (node (ref "IC10") (pin "62") (pinfunction "PB9/SPI2_NSS/I2S2_WS/I2C1_SDA/TIM4_CH4_62") (pintype "bidirectional"))
    )
    (net (code "136") (name "unconnected-(IC10-PC8-Pad39)") (class "Default")
      (node (ref "IC10") (pin "39") (pinfunction "PC8_39") (pintype "bidirectional"))
    )
    (net (code "137") (name "unconnected-(IC10-PC9{slash}I2S2_CKIN{slash}I2S3_CKIN-Pad40)") (class "Default")
      (node (ref "IC10") (pin "40") (pinfunction "PC9/I2S2_CKIN/I2S3_CKIN_40") (pintype "bidirectional"))
    )
    (net (code "138") (name "unconnected-(IC10-PC10{slash}SPI3_SCK{slash}I2S3_SCK{slash}UART4_TX-Pad51)") (class "Default")
      (node (ref "IC10") (pin "51") (pinfunction "PC10/SPI3_SCK/I2S3_SCK/UART4_TX_51") (pintype "bidirectional"))
    )
    (net (code "139") (name "unconnected-(IC10-PC11{slash}UART4_RX{slash}SPI3_MISO{slash}USART3_RX-Pad52)") (class "Default")
      (node (ref "IC10") (pin "52") (pinfunction "PC11/UART4_RX/SPI3_MISO/USART3_RX_52") (pintype "bidirectional"))
    )
    (net (code "140") (name "unconnected-(IC10-PC12{slash}UART5_TX{slash}I2S3_SD{slash}USART3_CK-Pad53)") (class "Default")
      (node (ref "IC10") (pin "53") (pinfunction "PC12/UART5_TX/I2S3_SD/USART3_CK_53") (pintype "bidirectional"))
    )
    (net (code "141") (name "unconnected-(IC10-PD2{slash}TIM3-ETR-Pad54)") (class "Default")
      (node (ref "IC10") (pin "54") (pinfunction "PD2/TIM3-ETR_54") (pintype "bidirectional"))
    )
    (net (code "142") (name "unconnected-(IC12-CLKOUT-Pad2)") (class "Default")
      (node (ref "IC12") (pin "2") (pinfunction "CLKOUT_2") (pintype "bidirectional"))
    )
    (net (code "143") (name "unconnected-(IC12-LHPOUT-Pad9)") (class "Default")
      (node (ref "IC12") (pin "9") (pinfunction "LHPOUT_9") (pintype "bidirectional"))
    )
    (net (code "144") (name "unconnected-(IC12-MICBIAS-Pad17)") (class "Default")
      (node (ref "IC12") (pin "17") (pinfunction "MICBIAS_17") (pintype "bidirectional"))
    )
    (net (code "145") (name "unconnected-(IC12-MICIN-Pad18)") (class "Default")
      (node (ref "IC12") (pin "18") (pinfunction "MICIN_18") (pintype "bidirectional"))
    )
    (net (code "146") (name "unconnected-(IC12-RHPOUT-Pad10)") (class "Default")
      (node (ref "IC12") (pin "10") (pinfunction "RHPOUT_10") (pintype "bidirectional"))
    )
    (net (code "147") (name "unconnected-(IC12-XTO-Pad26)") (class "Default")
      (node (ref "IC12") (pin "26") (pinfunction "XTO_26") (pintype "bidirectional"))
    )
    (net (code "148") (name "unconnected-(J1-2-PadP2)") (class "Default")
      (node (ref "J1") (pin "P2") (pinfunction "2_P2") (pintype "passive"))
    )
    (net (code "149") (name "unconnected-(J2-2-PadP2)") (class "Default")
      (node (ref "J2") (pin "P2") (pinfunction "2_P2") (pintype "passive"))
    )
    (net (code "150") (name "unconnected-(J4-2-PadP2)") (class "Default")
      (node (ref "J4") (pin "P2") (pinfunction "2_P2") (pintype "passive"))
    )
    (net (code "151") (name "unconnected-(J5-2-PadP2)") (class "Default")
      (node (ref "J5") (pin "P2") (pinfunction "2_P2") (pintype "passive"))
    )
    (net (code "152") (name "unconnected-(J6-2-PadP2)") (class "Default")
      (node (ref "J6") (pin "P2") (pinfunction "2_P2") (pintype "passive"))
    )
    (net (code "153") (name "unconnected-(J7-2-PadP2)") (class "Default")
      (node (ref "J7") (pin "P2") (pinfunction "2_P2") (pintype "passive"))
    )
    (net (code "154") (name "unconnected-(J8-2-PadP2)") (class "Default")
      (node (ref "J8") (pin "P2") (pinfunction "2_P2") (pintype "passive"))
    )
    (net (code "155") (name "unconnected-(J9-2-PadP2)") (class "Default")
      (node (ref "J9") (pin "P2") (pinfunction "2_P2") (pintype "passive"))
    )
    (net (code "156") (name "unconnected-(J10-2-PadP2)") (class "Default")
      (node (ref "J10") (pin "P2") (pinfunction "2_P2") (pintype "passive"))
    )
    (net (code "157") (name "unconnected-(J11-2-PadP2)") (class "Default")
      (node (ref "J11") (pin "P2") (pinfunction "2_P2") (pintype "passive"))
    )
    (net (code "158") (name "unconnected-(J12-2-PadP2)") (class "Default")
      (node (ref "J12") (pin "P2") (pinfunction "2_P2") (pintype "passive"))
    )
    (net (code "159") (name "unconnected-(J13-2-PadP2)") (class "Default")
      (node (ref "J13") (pin "P2") (pinfunction "2_P2") (pintype "passive"))
    )
    (net (code "160") (name "unconnected-(J14-2-PadP2)") (class "Default")
      (node (ref "J14") (pin "P2") (pinfunction "2_P2") (pintype "passive"))
    )
    (net (code "161") (name "unconnected-(J15-2-PadP2)") (class "Default")
      (node (ref "J15") (pin "P2") (pinfunction "2_P2") (pintype "passive"))
    )
    (net (code "162") (name "unconnected-(J16-2-PadP2)") (class "Default")
      (node (ref "J16") (pin "P2") (pinfunction "2_P2") (pintype "passive"))
    )
    (net (code "163") (name "unconnected-(J17-2-PadP2)") (class "Default")
      (node (ref "J17") (pin "P2") (pinfunction "2_P2") (pintype "passive"))
    )
    (net (code "164") (name "unconnected-(J18-2-PadP2)") (class "Default")
      (node (ref "J18") (pin "P2") (pinfunction "2_P2") (pintype "passive"))
    )
    (net (code "165") (name "unconnected-(JP1-Pad7)") (class "Default")
      (node (ref "JP1") (pin "7") (pinfunction "7_7") (pintype "passive"))
    )
    (net (code "166") (name "unconnected-(JP2-Pad2)") (class "Default")
      (node (ref "JP2") (pin "2") (pinfunction "2_2") (pintype "passive"))
    )
    (net (code "167") (name "unconnected-(JP2-Pad3)") (class "Default")
      (node (ref "JP2") (pin "3") (pinfunction "3_3") (pintype "passive"))
    )
    (net (code "168") (name "unconnected-(JP2-Pad6)") (class "Default")
      (node (ref "JP2") (pin "6") (pinfunction "6_6") (pintype "passive"))
    )
    (net (code "169") (name "unconnected-(SW1A-A1-PadP1)") (class "Default")
      (node (ref "SW1") (pin "P1") (pinfunction "A1_P1") (pintype "passive"))
    )
    (net (code "170") (name "unconnected-(SW1A-B1-PadP4)") (class "Default")
      (node (ref "SW1") (pin "P4") (pinfunction "B1_P4") (pintype "passive"))
    )
  )
)
